# dw08a.net
KiCad netlist of a schematic drawn in EAGLE
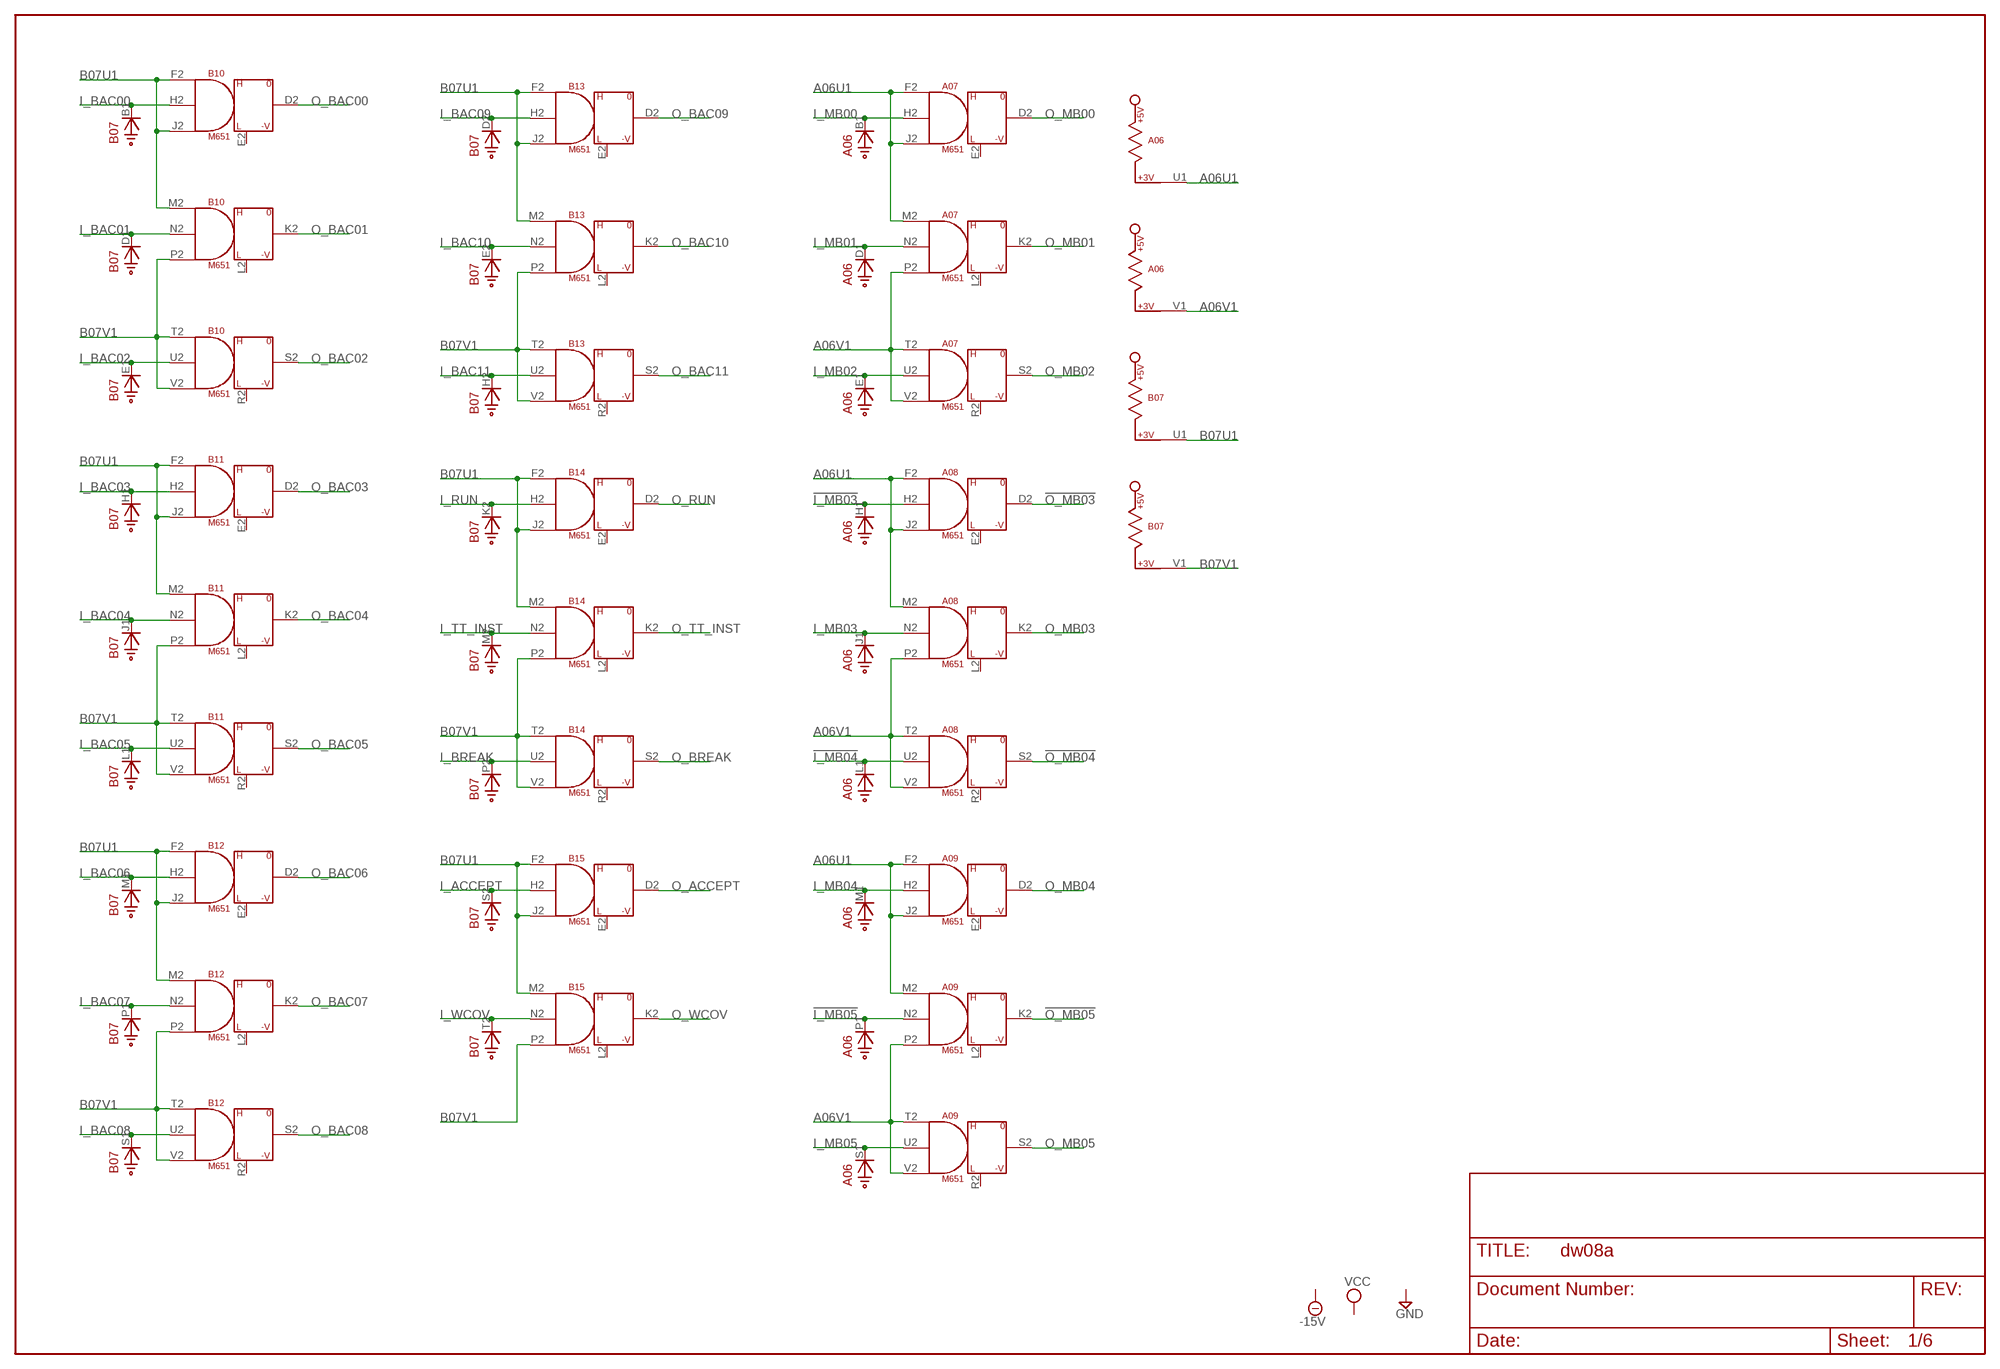
[diagram p0: schematic, sheet 1]
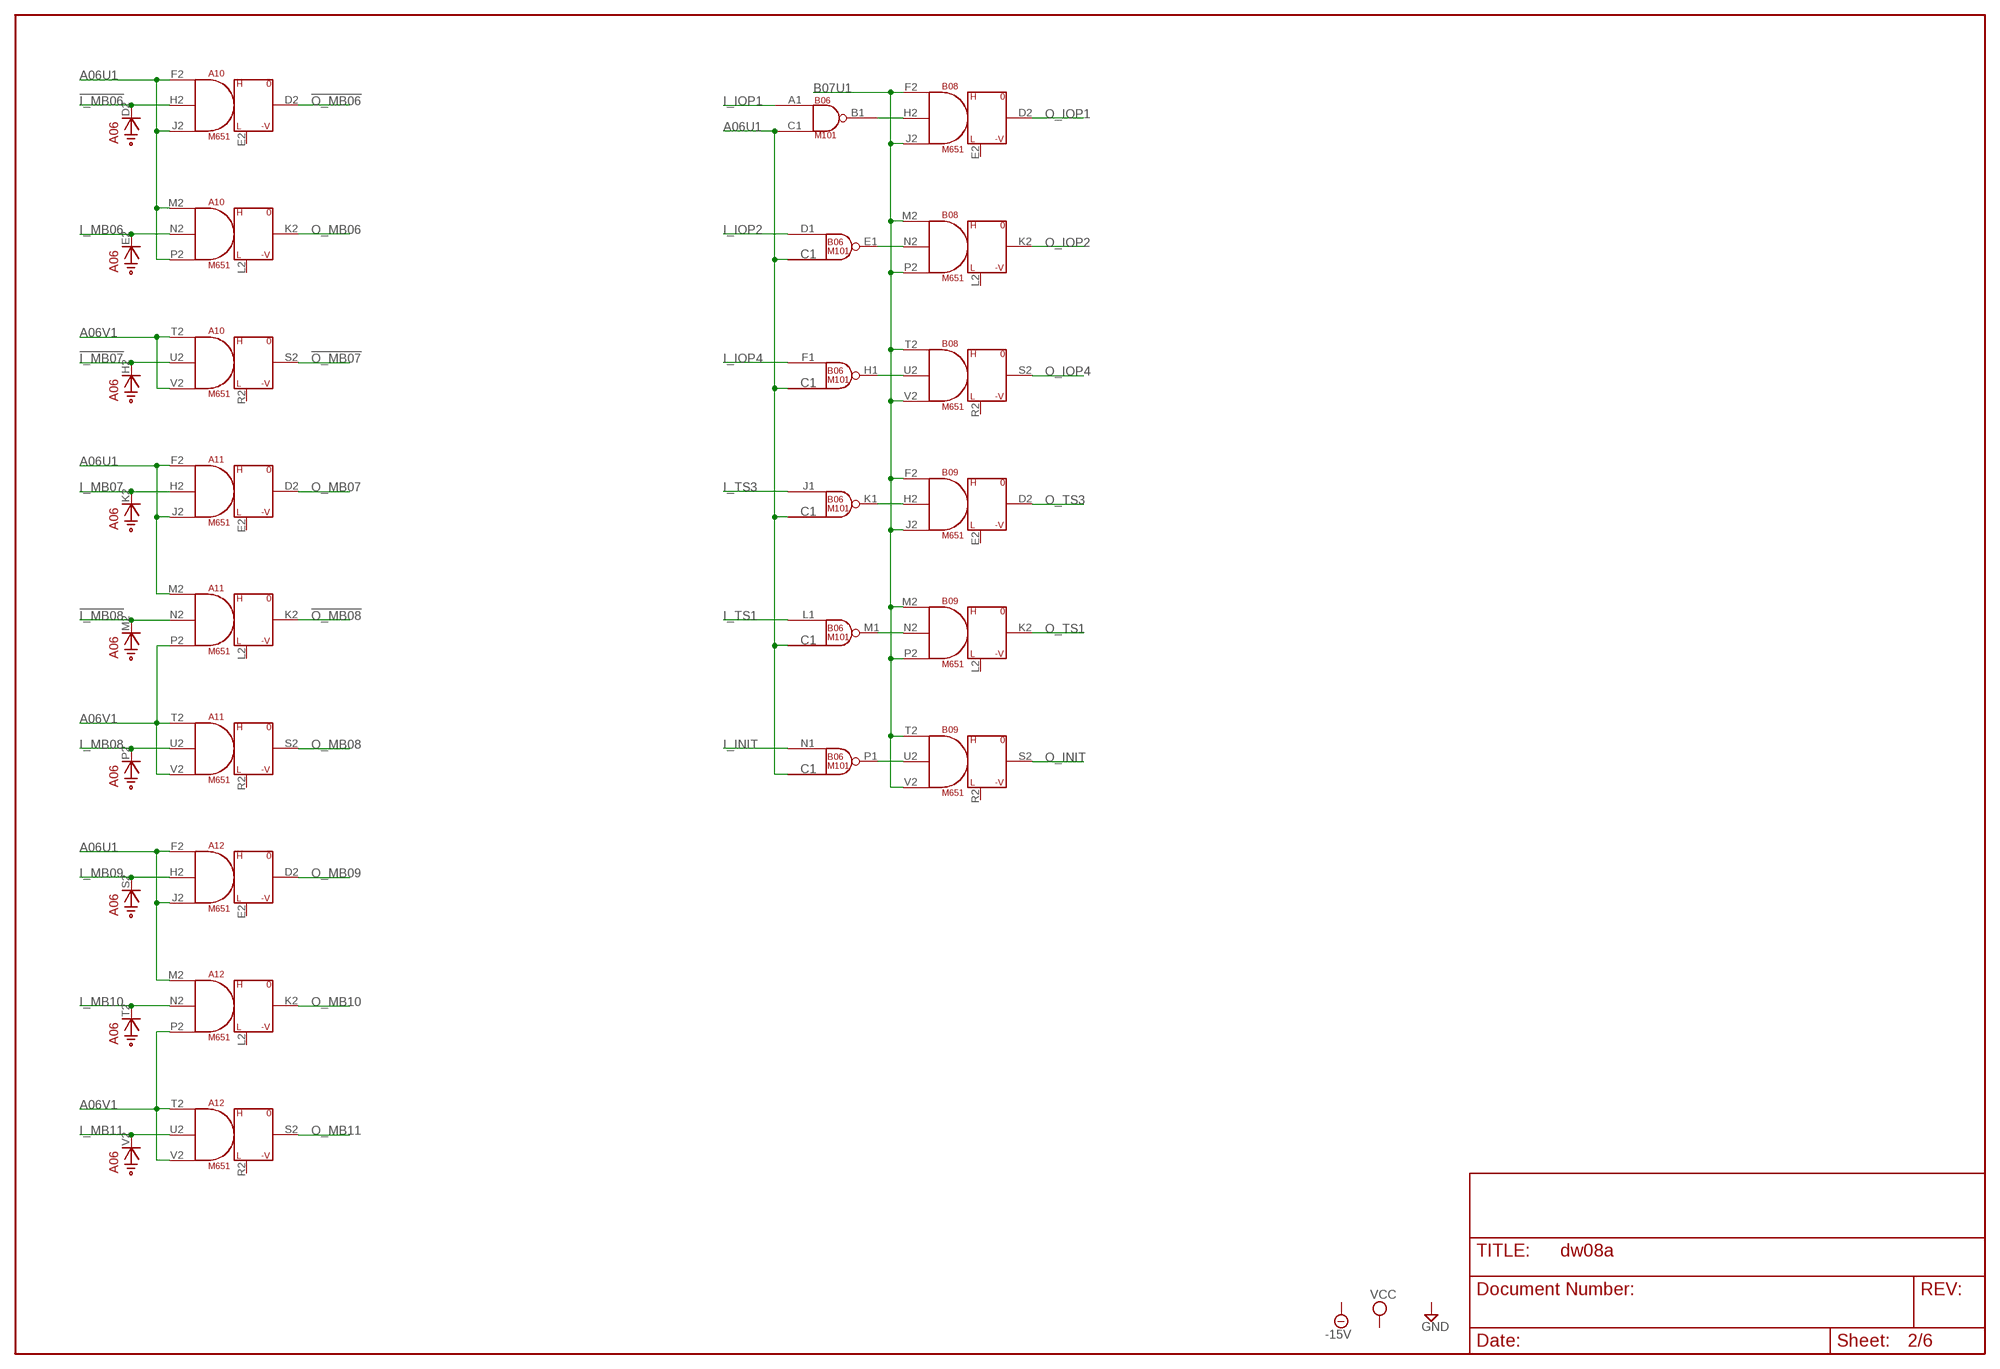
[diagram p1: schematic, sheet 2]
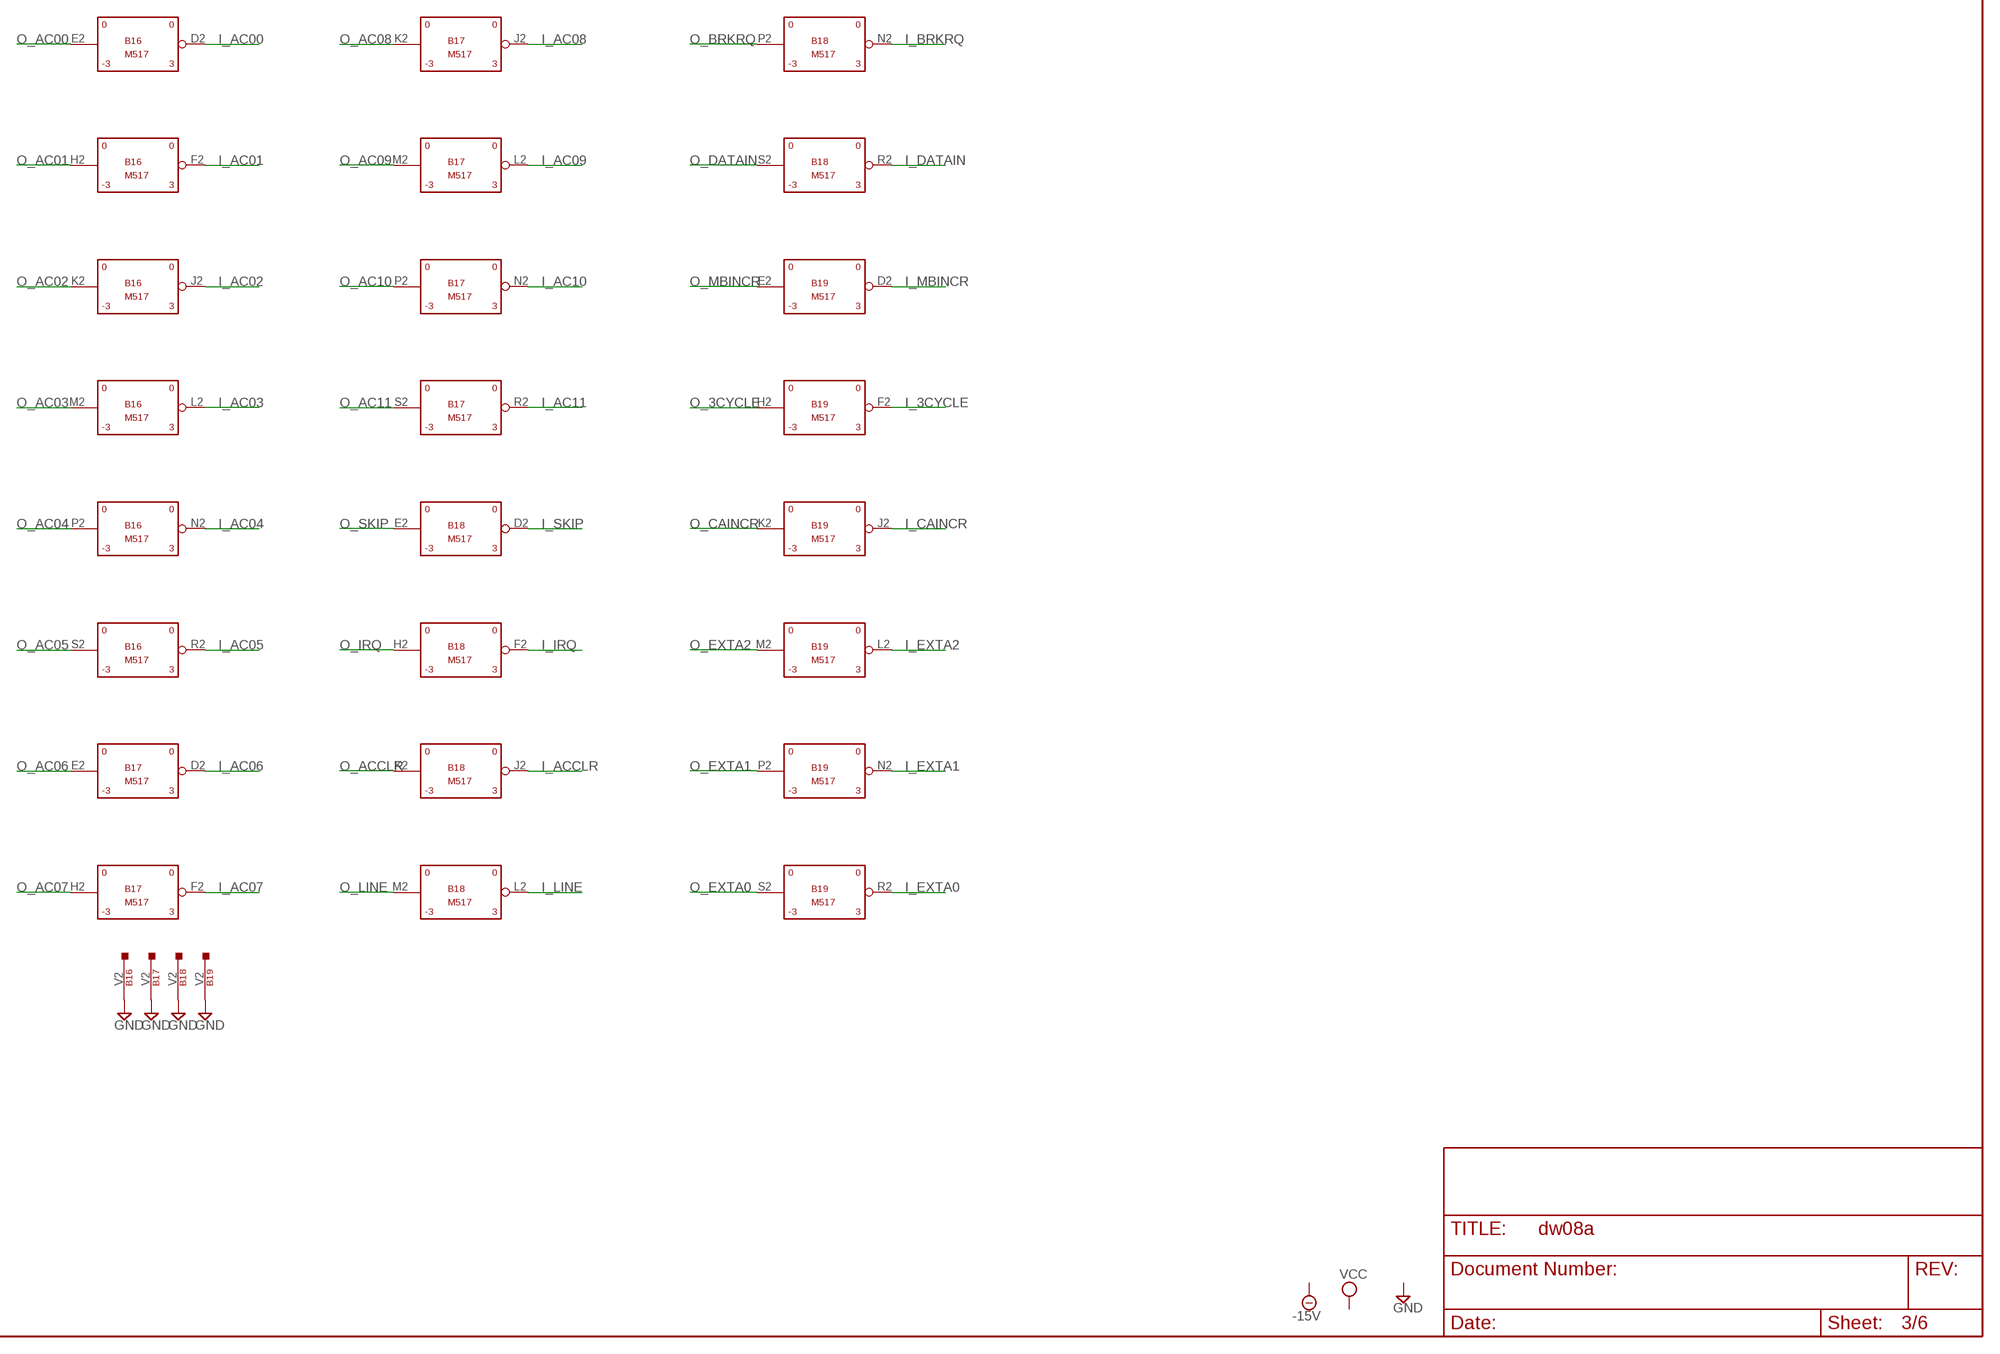
[diagram p2: schematic, sheet 3]
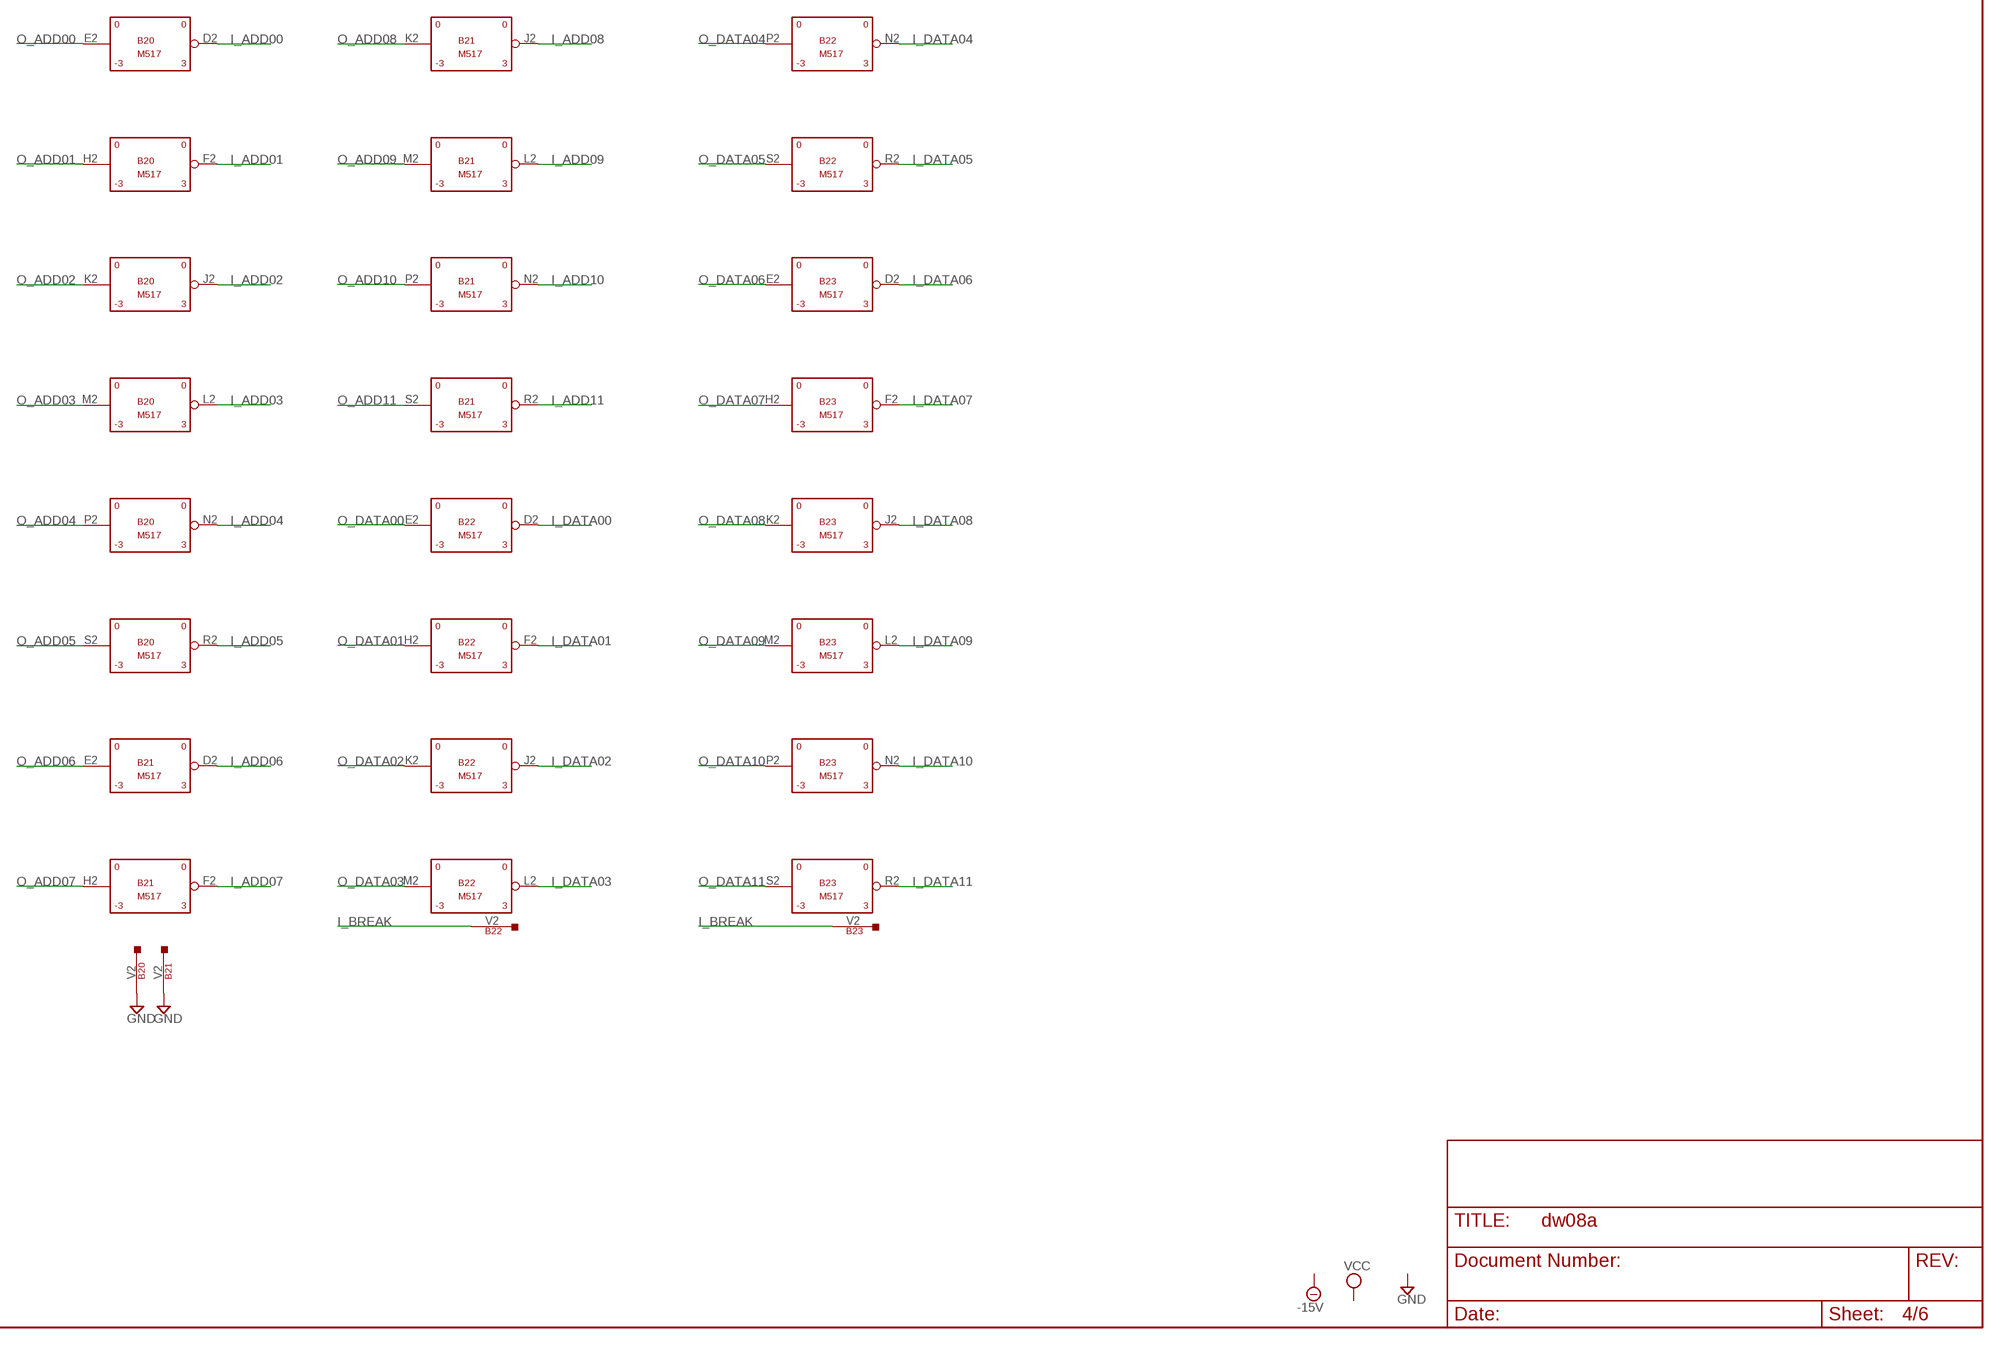
[diagram p3: schematic, sheet 4]
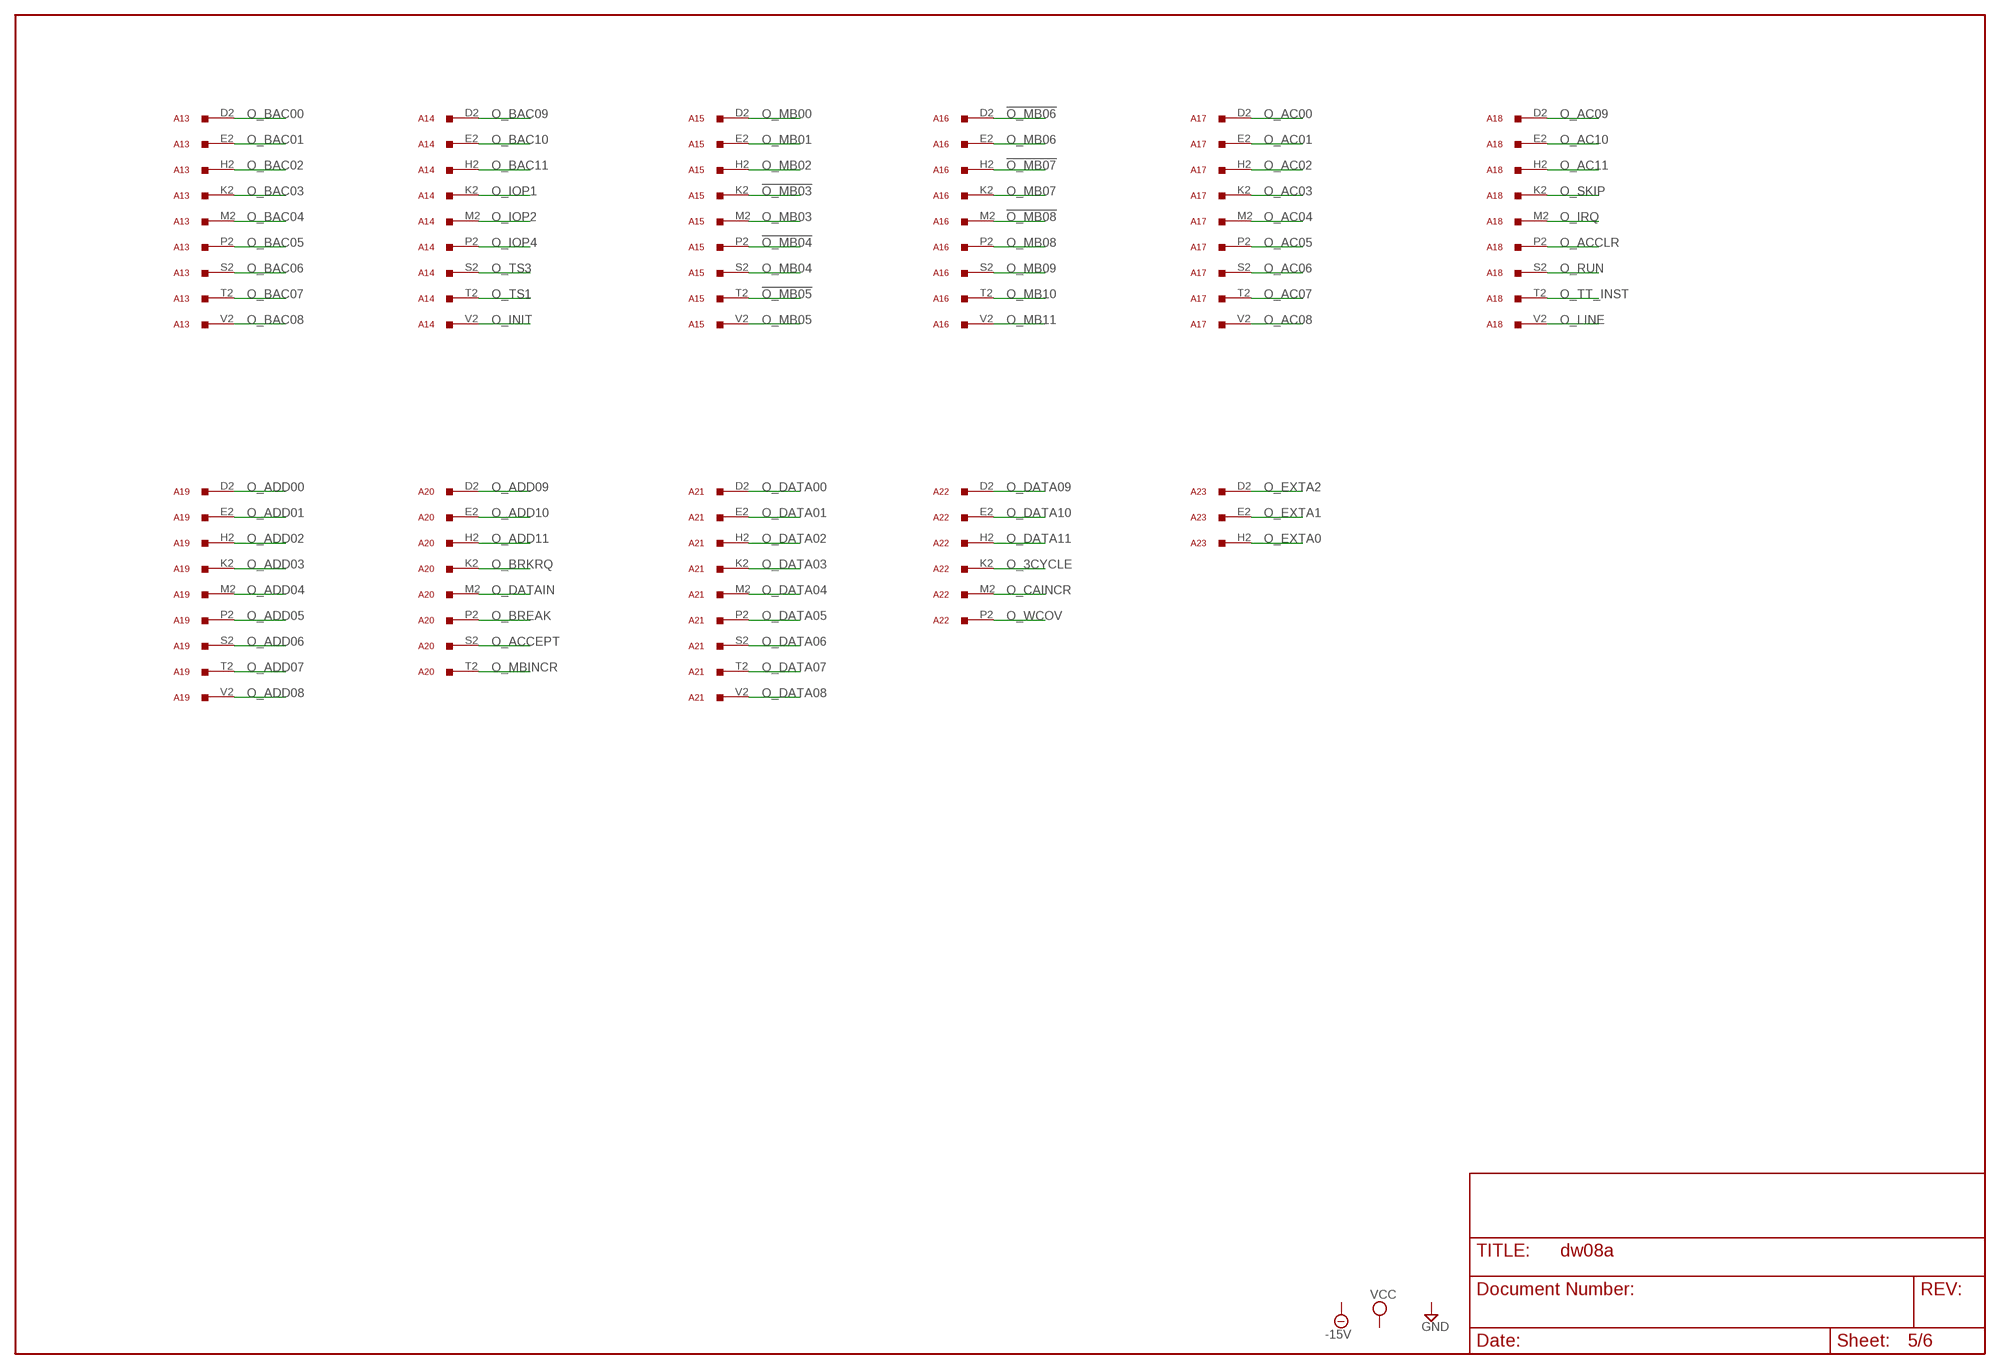
[diagram p4: schematic, sheet 5]
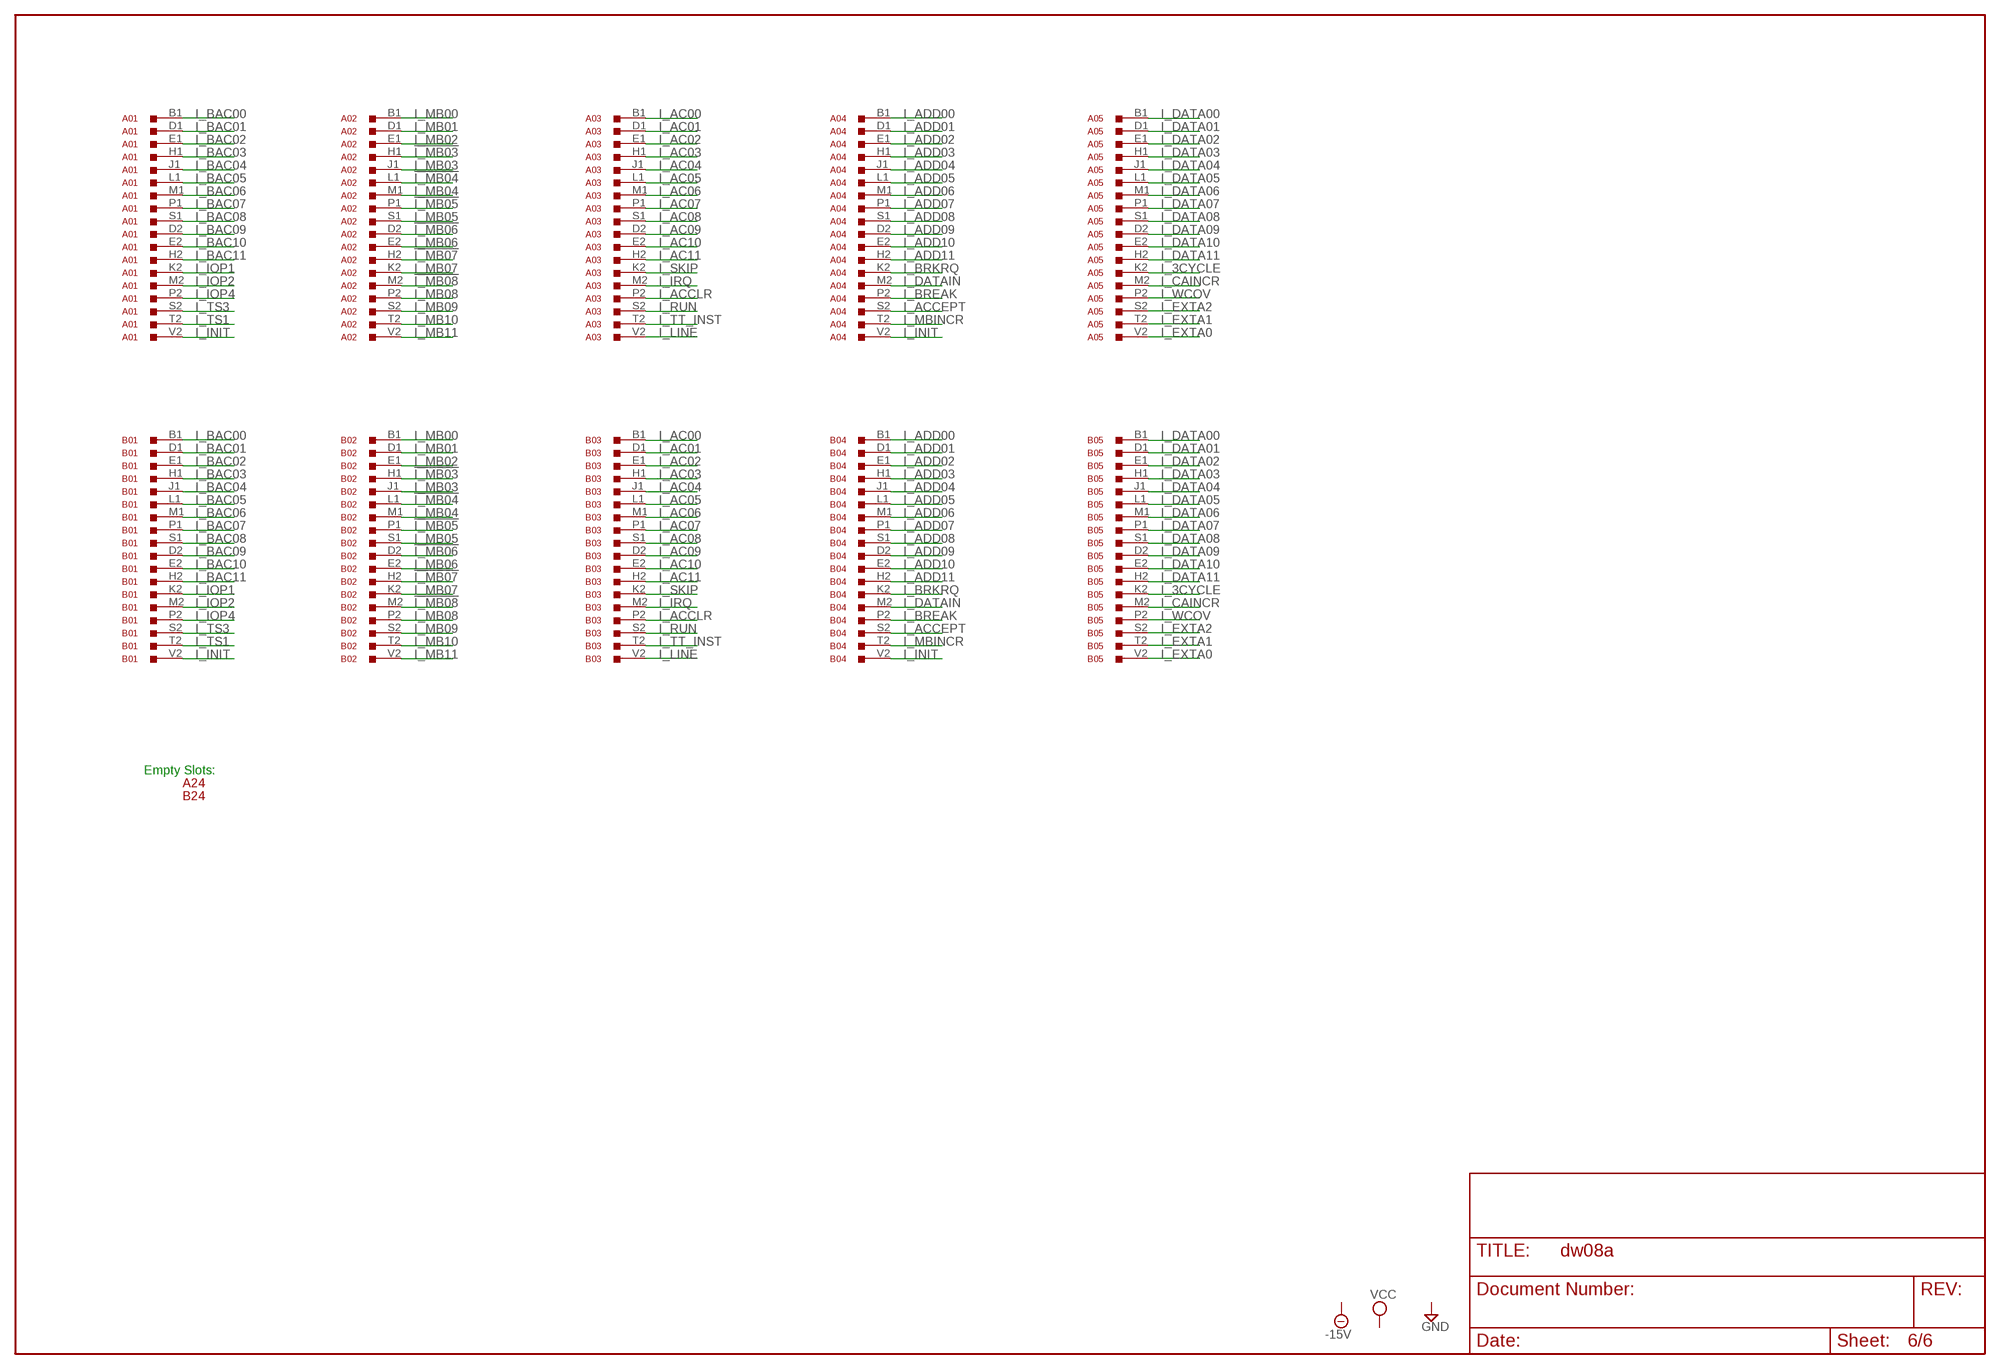
[diagram p5: schematic, sheet 6]

(export (version "E")
  (design (tool "Eeschema 10.0.6"))
  (components
    (comp (ref "A06")
      (value "M907")
      (footprint "eagle-import:H807")
      (libsource (lib "eagle-import") (part "M907"))
    )
    (comp (ref "A07")
      (value "M651")
      (footprint "eagle-import:H807")
      (libsource (lib "eagle-import") (part "M651"))
    )
    (comp (ref "A08")
      (value "M651")
      (footprint "eagle-import:H807")
      (libsource (lib "eagle-import") (part "M651"))
    )
    (comp (ref "A09")
      (value "M651")
      (footprint "eagle-import:H807")
      (libsource (lib "eagle-import") (part "M651"))
    )
    (comp (ref "B07")
      (value "M907")
      (footprint "eagle-import:H807")
      (libsource (lib "eagle-import") (part "M907"))
    )
    (comp (ref "B10")
      (value "M651")
      (footprint "eagle-import:H807")
      (libsource (lib "eagle-import") (part "M651"))
    )
    (comp (ref "B11")
      (value "M651")
      (footprint "eagle-import:H807")
      (libsource (lib "eagle-import") (part "M651"))
    )
    (comp (ref "B12")
      (value "M651")
      (footprint "eagle-import:H807")
      (libsource (lib "eagle-import") (part "M651"))
    )
    (comp (ref "B13")
      (value "M651")
      (footprint "eagle-import:H807")
      (libsource (lib "eagle-import") (part "M651"))
    )
    (comp (ref "B14")
      (value "M651")
      (footprint "eagle-import:H807")
      (libsource (lib "eagle-import") (part "M651"))
    )
    (comp (ref "B15")
      (value "M651")
      (footprint "eagle-import:H807")
      (libsource (lib "eagle-import") (part "M651"))
    )
    (comp (ref "B16")
      (value "M517")
      (footprint "eagle-import:H807")
      (libsource (lib "eagle-import") (part "M517"))
    )
    (comp (ref "B17")
      (value "M517")
      (footprint "eagle-import:H807")
      (libsource (lib "eagle-import") (part "M517"))
    )
    (comp (ref "B18")
      (value "M517")
      (footprint "eagle-import:H807")
      (libsource (lib "eagle-import") (part "M517"))
    )
    (comp (ref "B19")
      (value "M517")
      (footprint "eagle-import:H807")
      (libsource (lib "eagle-import") (part "M517"))
    )
    (comp (ref "A01")
      (value "M903")
      (footprint "eagle-import:H807")
      (libsource (lib "eagle-import") (part "M903"))
    )
    (comp (ref "A02")
      (value "M903")
      (footprint "eagle-import:H807")
      (libsource (lib "eagle-import") (part "M903"))
    )
    (comp (ref "A03")
      (value "M903")
      (footprint "eagle-import:H807")
      (libsource (lib "eagle-import") (part "M903"))
    )
    (comp (ref "A04")
      (value "M903")
      (footprint "eagle-import:H807")
      (libsource (lib "eagle-import") (part "M903"))
    )
    (comp (ref "A05")
      (value "M903")
      (footprint "eagle-import:H807")
      (libsource (lib "eagle-import") (part "M903"))
    )
    (comp (ref "A24")
      (value "H807")
      (footprint "eagle-import:H807")
      (libsource (lib "eagle-import") (part "H807"))
    )
    (comp (ref "B01")
      (value "M903")
      (footprint "eagle-import:H807")
      (libsource (lib "eagle-import") (part "M903"))
    )
    (comp (ref "B02")
      (value "M903")
      (footprint "eagle-import:H807")
      (libsource (lib "eagle-import") (part "M903"))
    )
    (comp (ref "B03")
      (value "M903")
      (footprint "eagle-import:H807")
      (libsource (lib "eagle-import") (part "M903"))
    )
    (comp (ref "B04")
      (value "M903")
      (footprint "eagle-import:H807")
      (libsource (lib "eagle-import") (part "M903"))
    )
    (comp (ref "B05")
      (value "M903")
      (footprint "eagle-import:H807")
      (libsource (lib "eagle-import") (part "M903"))
    )
    (comp (ref "B24")
      (value "H807")
      (footprint "eagle-import:H807")
      (libsource (lib "eagle-import") (part "H807"))
    )
    (comp (ref "A10")
      (value "M651")
      (footprint "eagle-import:H807")
      (libsource (lib "eagle-import") (part "M651"))
    )
    (comp (ref "A11")
      (value "M651")
      (footprint "eagle-import:H807")
      (libsource (lib "eagle-import") (part "M651"))
    )
    (comp (ref "A12")
      (value "M651")
      (footprint "eagle-import:H807")
      (libsource (lib "eagle-import") (part "M651"))
    )
    (comp (ref "B06")
      (value "M101")
      (footprint "eagle-import:H807")
      (libsource (lib "eagle-import") (part "M101"))
    )
    (comp (ref "B08")
      (value "M651")
      (footprint "eagle-import:H807")
      (libsource (lib "eagle-import") (part "M651"))
    )
    (comp (ref "B09")
      (value "M651")
      (footprint "eagle-import:H807")
      (libsource (lib "eagle-import") (part "M651"))
    )
    (comp (ref "B20")
      (value "M517")
      (footprint "eagle-import:H807")
      (libsource (lib "eagle-import") (part "M517"))
    )
    (comp (ref "B21")
      (value "M517")
      (footprint "eagle-import:H807")
      (libsource (lib "eagle-import") (part "M517"))
    )
    (comp (ref "B22")
      (value "M517")
      (footprint "eagle-import:H807")
      (libsource (lib "eagle-import") (part "M517"))
    )
    (comp (ref "B23")
      (value "M517")
      (footprint "eagle-import:H807")
      (libsource (lib "eagle-import") (part "M517"))
    )
    (comp (ref "A13")
      (value "W011")
      (footprint "eagle-import:H807")
      (libsource (lib "eagle-import") (part "W011"))
    )
    (comp (ref "A14")
      (value "W011")
      (footprint "eagle-import:H807")
      (libsource (lib "eagle-import") (part "W011"))
    )
    (comp (ref "A15")
      (value "W011")
      (footprint "eagle-import:H807")
      (libsource (lib "eagle-import") (part "W011"))
    )
    (comp (ref "A16")
      (value "W011")
      (footprint "eagle-import:H807")
      (libsource (lib "eagle-import") (part "W011"))
    )
    (comp (ref "A17")
      (value "W011")
      (footprint "eagle-import:H807")
      (libsource (lib "eagle-import") (part "W011"))
    )
    (comp (ref "A18")
      (value "W011")
      (footprint "eagle-import:H807")
      (libsource (lib "eagle-import") (part "W011"))
    )
    (comp (ref "A19")
      (value "W011")
      (footprint "eagle-import:H807")
      (libsource (lib "eagle-import") (part "W011"))
    )
    (comp (ref "A20")
      (value "W011")
      (footprint "eagle-import:H807")
      (libsource (lib "eagle-import") (part "W011"))
    )
    (comp (ref "A21")
      (value "W011")
      (footprint "eagle-import:H807")
      (libsource (lib "eagle-import") (part "W011"))
    )
    (comp (ref "A22")
      (value "W011")
      (footprint "eagle-import:H807")
      (libsource (lib "eagle-import") (part "W011"))
    )
    (comp (ref "A23")
      (value "W011")
      (footprint "eagle-import:H807")
      (libsource (lib "eagle-import") (part "W011"))
    )
  )
  (nets
    (net (code "2") (name "A06U1") (class "Default")
      (node (ref "A06") (pin "U1") (pinfunction "P$1_U1") (pintype "passive"))
      (node (ref "A07") (pin "F2") (pinfunction "IN1_F2") (pintype "input"))
      (node (ref "A07") (pin "J2") (pinfunction "IN3_J2") (pintype "input"))
      (node (ref "A07") (pin "M2") (pinfunction "IN1_M2") (pintype "input"))
      (node (ref "A08") (pin "F2") (pinfunction "IN1_F2") (pintype "input"))
      (node (ref "A08") (pin "J2") (pinfunction "IN3_J2") (pintype "input"))
      (node (ref "A08") (pin "M2") (pinfunction "IN1_M2") (pintype "input"))
      (node (ref "A09") (pin "F2") (pinfunction "IN1_F2") (pintype "input"))
      (node (ref "A09") (pin "J2") (pinfunction "IN3_J2") (pintype "input"))
      (node (ref "A09") (pin "M2") (pinfunction "IN1_M2") (pintype "input"))
      (node (ref "A10") (pin "F2") (pinfunction "IN1_F2") (pintype "input"))
      (node (ref "A10") (pin "J2") (pinfunction "IN3_J2") (pintype "input"))
      (node (ref "A10") (pin "M2") (pinfunction "IN1_M2") (pintype "input"))
      (node (ref "A10") (pin "P2") (pinfunction "IN3_P2") (pintype "input"))
      (node (ref "A11") (pin "F2") (pinfunction "IN1_F2") (pintype "input"))
      (node (ref "A11") (pin "J2") (pinfunction "IN3_J2") (pintype "input"))
      (node (ref "A11") (pin "M2") (pinfunction "IN1_M2") (pintype "input"))
      (node (ref "A12") (pin "F2") (pinfunction "IN1_F2") (pintype "input"))
      (node (ref "A12") (pin "J2") (pinfunction "IN3_J2") (pintype "input"))
      (node (ref "A12") (pin "M2") (pinfunction "IN1_M2") (pintype "input"))
      (node (ref "B06") (pin "C1") (pinfunction "IN2_C1") (pintype "input"))
    )
    (net (code "3") (name "A06V1") (class "Default")
      (node (ref "A06") (pin "V1") (pinfunction "P$1_V1") (pintype "passive"))
      (node (ref "A07") (pin "P2") (pinfunction "IN3_P2") (pintype "input"))
      (node (ref "A07") (pin "T2") (pinfunction "IN1_T2") (pintype "input"))
      (node (ref "A07") (pin "V2") (pinfunction "IN3_V2") (pintype "input"))
      (node (ref "A08") (pin "P2") (pinfunction "IN3_P2") (pintype "input"))
      (node (ref "A08") (pin "T2") (pinfunction "IN1_T2") (pintype "input"))
      (node (ref "A08") (pin "V2") (pinfunction "IN3_V2") (pintype "input"))
      (node (ref "A09") (pin "P2") (pinfunction "IN3_P2") (pintype "input"))
      (node (ref "A09") (pin "T2") (pinfunction "IN1_T2") (pintype "input"))
      (node (ref "A09") (pin "V2") (pinfunction "IN3_V2") (pintype "input"))
      (node (ref "A10") (pin "T2") (pinfunction "IN1_T2") (pintype "input"))
      (node (ref "A10") (pin "V2") (pinfunction "IN3_V2") (pintype "input"))
      (node (ref "A11") (pin "P2") (pinfunction "IN3_P2") (pintype "input"))
      (node (ref "A11") (pin "T2") (pinfunction "IN1_T2") (pintype "input"))
      (node (ref "A11") (pin "V2") (pinfunction "IN3_V2") (pintype "input"))
      (node (ref "A12") (pin "P2") (pinfunction "IN3_P2") (pintype "input"))
      (node (ref "A12") (pin "T2") (pinfunction "IN1_T2") (pintype "input"))
      (node (ref "A12") (pin "V2") (pinfunction "IN3_V2") (pintype "input"))
    )
    (net (code "4") (name "B07U1") (class "Default")
      (node (ref "B07") (pin "U1") (pinfunction "P$1_U1") (pintype "passive"))
      (node (ref "B08") (pin "F2") (pinfunction "IN1_F2") (pintype "input"))
      (node (ref "B08") (pin "J2") (pinfunction "IN3_J2") (pintype "input"))
      (node (ref "B08") (pin "M2") (pinfunction "IN1_M2") (pintype "input"))
      (node (ref "B08") (pin "P2") (pinfunction "IN3_P2") (pintype "input"))
      (node (ref "B08") (pin "T2") (pinfunction "IN1_T2") (pintype "input"))
      (node (ref "B08") (pin "V2") (pinfunction "IN3_V2") (pintype "input"))
      (node (ref "B09") (pin "F2") (pinfunction "IN1_F2") (pintype "input"))
      (node (ref "B09") (pin "J2") (pinfunction "IN3_J2") (pintype "input"))
      (node (ref "B09") (pin "M2") (pinfunction "IN1_M2") (pintype "input"))
      (node (ref "B09") (pin "P2") (pinfunction "IN3_P2") (pintype "input"))
      (node (ref "B09") (pin "T2") (pinfunction "IN1_T2") (pintype "input"))
      (node (ref "B09") (pin "V2") (pinfunction "IN3_V2") (pintype "input"))
      (node (ref "B10") (pin "F2") (pinfunction "IN1_F2") (pintype "input"))
      (node (ref "B10") (pin "J2") (pinfunction "IN3_J2") (pintype "input"))
      (node (ref "B10") (pin "M2") (pinfunction "IN1_M2") (pintype "input"))
      (node (ref "B11") (pin "F2") (pinfunction "IN1_F2") (pintype "input"))
      (node (ref "B11") (pin "J2") (pinfunction "IN3_J2") (pintype "input"))
      (node (ref "B11") (pin "M2") (pinfunction "IN1_M2") (pintype "input"))
      (node (ref "B12") (pin "F2") (pinfunction "IN1_F2") (pintype "input"))
      (node (ref "B12") (pin "J2") (pinfunction "IN3_J2") (pintype "input"))
      (node (ref "B12") (pin "M2") (pinfunction "IN1_M2") (pintype "input"))
      (node (ref "B13") (pin "F2") (pinfunction "IN1_F2") (pintype "input"))
      (node (ref "B13") (pin "J2") (pinfunction "IN3_J2") (pintype "input"))
      (node (ref "B13") (pin "M2") (pinfunction "IN1_M2") (pintype "input"))
      (node (ref "B14") (pin "F2") (pinfunction "IN1_F2") (pintype "input"))
      (node (ref "B14") (pin "J2") (pinfunction "IN3_J2") (pintype "input"))
      (node (ref "B14") (pin "M2") (pinfunction "IN1_M2") (pintype "input"))
      (node (ref "B15") (pin "F2") (pinfunction "IN1_F2") (pintype "input"))
      (node (ref "B15") (pin "J2") (pinfunction "IN3_J2") (pintype "input"))
      (node (ref "B15") (pin "M2") (pinfunction "IN1_M2") (pintype "input"))
    )
    (net (code "5") (name "B07V1") (class "Default")
      (node (ref "B07") (pin "V1") (pinfunction "P$1_V1") (pintype "passive"))
      (node (ref "B10") (pin "P2") (pinfunction "IN3_P2") (pintype "input"))
      (node (ref "B10") (pin "T2") (pinfunction "IN1_T2") (pintype "input"))
      (node (ref "B10") (pin "V2") (pinfunction "IN3_V2") (pintype "input"))
      (node (ref "B11") (pin "P2") (pinfunction "IN3_P2") (pintype "input"))
      (node (ref "B11") (pin "T2") (pinfunction "IN1_T2") (pintype "input"))
      (node (ref "B11") (pin "V2") (pinfunction "IN3_V2") (pintype "input"))
      (node (ref "B12") (pin "P2") (pinfunction "IN3_P2") (pintype "input"))
      (node (ref "B12") (pin "T2") (pinfunction "IN1_T2") (pintype "input"))
      (node (ref "B12") (pin "V2") (pinfunction "IN3_V2") (pintype "input"))
      (node (ref "B13") (pin "P2") (pinfunction "IN3_P2") (pintype "input"))
      (node (ref "B13") (pin "T2") (pinfunction "IN1_T2") (pintype "input"))
      (node (ref "B13") (pin "V2") (pinfunction "IN3_V2") (pintype "input"))
      (node (ref "B14") (pin "P2") (pinfunction "IN3_P2") (pintype "input"))
      (node (ref "B14") (pin "T2") (pinfunction "IN1_T2") (pintype "input"))
      (node (ref "B14") (pin "V2") (pinfunction "IN3_V2") (pintype "input"))
      (node (ref "B15") (pin "P2") (pinfunction "IN3_P2") (pintype "input"))
    )
    (net (code "6") (name "GND") (class "Default")
      (node (ref "B16") (pin "V2") (pinfunction "P$1_V2") (pintype "input"))
      (node (ref "B17") (pin "V2") (pinfunction "P$1_V2") (pintype "input"))
      (node (ref "B18") (pin "V2") (pinfunction "P$1_V2") (pintype "input"))
      (node (ref "B19") (pin "V2") (pinfunction "P$1_V2") (pintype "input"))
      (node (ref "B20") (pin "V2") (pinfunction "P$1_V2") (pintype "input"))
      (node (ref "B21") (pin "V2") (pinfunction "P$1_V2") (pintype "input"))
    )
    (net (code "7") (name "I_3CYCLE") (class "Default")
      (node (ref "A05") (pin "K2") (pinfunction "P$2_K2") (pintype "bidirectional"))
      (node (ref "B05") (pin "K2") (pinfunction "P$2_K2") (pintype "bidirectional"))
      (node (ref "B19") (pin "F2") (pinfunction "OUT_F2") (pintype "output"))
    )
    (net (code "8") (name "I_AC00") (class "Default")
      (node (ref "A03") (pin "B1") (pinfunction "P$2_B1") (pintype "bidirectional"))
      (node (ref "B03") (pin "B1") (pinfunction "P$2_B1") (pintype "bidirectional"))
      (node (ref "B16") (pin "D2") (pinfunction "OUT_D2") (pintype "output"))
    )
    (net (code "9") (name "I_AC01") (class "Default")
      (node (ref "A03") (pin "D1") (pinfunction "P$2_D1") (pintype "bidirectional"))
      (node (ref "B03") (pin "D1") (pinfunction "P$2_D1") (pintype "bidirectional"))
      (node (ref "B16") (pin "F2") (pinfunction "OUT_F2") (pintype "output"))
    )
    (net (code "10") (name "I_AC02") (class "Default")
      (node (ref "A03") (pin "E1") (pinfunction "P$2_E1") (pintype "bidirectional"))
      (node (ref "B03") (pin "E1") (pinfunction "P$2_E1") (pintype "bidirectional"))
      (node (ref "B16") (pin "J2") (pinfunction "OUT_J2") (pintype "output"))
    )
    (net (code "11") (name "I_AC03") (class "Default")
      (node (ref "A03") (pin "H1") (pinfunction "P$2_H1") (pintype "bidirectional"))
      (node (ref "B03") (pin "H1") (pinfunction "P$2_H1") (pintype "bidirectional"))
      (node (ref "B16") (pin "L2") (pinfunction "OUT_L2") (pintype "output"))
    )
    (net (code "12") (name "I_AC04") (class "Default")
      (node (ref "A03") (pin "J1") (pinfunction "P$2_J1") (pintype "bidirectional"))
      (node (ref "B03") (pin "J1") (pinfunction "P$2_J1") (pintype "bidirectional"))
      (node (ref "B16") (pin "N2") (pinfunction "OUT_N2") (pintype "output"))
    )
    (net (code "13") (name "I_AC05") (class "Default")
      (node (ref "A03") (pin "L1") (pinfunction "P$2_L1") (pintype "bidirectional"))
      (node (ref "B03") (pin "L1") (pinfunction "P$2_L1") (pintype "bidirectional"))
      (node (ref "B16") (pin "R2") (pinfunction "OUT_R2") (pintype "output"))
    )
    (net (code "14") (name "I_AC06") (class "Default")
      (node (ref "A03") (pin "M1") (pinfunction "P$2_M1") (pintype "bidirectional"))
      (node (ref "B03") (pin "M1") (pinfunction "P$2_M1") (pintype "bidirectional"))
      (node (ref "B17") (pin "D2") (pinfunction "OUT_D2") (pintype "output"))
    )
    (net (code "15") (name "I_AC07") (class "Default")
      (node (ref "A03") (pin "P1") (pinfunction "P$2_P1") (pintype "bidirectional"))
      (node (ref "B03") (pin "P1") (pinfunction "P$2_P1") (pintype "bidirectional"))
      (node (ref "B17") (pin "F2") (pinfunction "OUT_F2") (pintype "output"))
    )
    (net (code "16") (name "I_AC08") (class "Default")
      (node (ref "A03") (pin "S1") (pinfunction "P$2_S1") (pintype "bidirectional"))
      (node (ref "B03") (pin "S1") (pinfunction "P$2_S1") (pintype "bidirectional"))
      (node (ref "B17") (pin "J2") (pinfunction "OUT_J2") (pintype "output"))
    )
    (net (code "17") (name "I_AC09") (class "Default")
      (node (ref "A03") (pin "D2") (pinfunction "P$2_D2") (pintype "bidirectional"))
      (node (ref "B03") (pin "D2") (pinfunction "P$2_D2") (pintype "bidirectional"))
      (node (ref "B17") (pin "L2") (pinfunction "OUT_L2") (pintype "output"))
    )
    (net (code "18") (name "I_AC10") (class "Default")
      (node (ref "A03") (pin "E2") (pinfunction "P$2_E2") (pintype "bidirectional"))
      (node (ref "B03") (pin "E2") (pinfunction "P$2_E2") (pintype "bidirectional"))
      (node (ref "B17") (pin "N2") (pinfunction "OUT_N2") (pintype "output"))
    )
    (net (code "19") (name "I_AC11") (class "Default")
      (node (ref "A03") (pin "H2") (pinfunction "P$2_H2") (pintype "bidirectional"))
      (node (ref "B03") (pin "H2") (pinfunction "P$2_H2") (pintype "bidirectional"))
      (node (ref "B17") (pin "R2") (pinfunction "OUT_R2") (pintype "output"))
    )
    (net (code "20") (name "I_ACCEPT") (class "Default")
      (node (ref "A04") (pin "S2") (pinfunction "P$2_S2") (pintype "bidirectional"))
      (node (ref "B04") (pin "S2") (pinfunction "P$2_S2") (pintype "bidirectional"))
      (node (ref "B07") (pin "S2") (pinfunction "CATHODE_S2") (pintype "passive"))
      (node (ref "B15") (pin "H2") (pinfunction "IN2_H2") (pintype "input"))
    )
    (net (code "21") (name "I_ACCLR") (class "Default")
      (node (ref "A03") (pin "P2") (pinfunction "P$2_P2") (pintype "bidirectional"))
      (node (ref "B03") (pin "P2") (pinfunction "P$2_P2") (pintype "bidirectional"))
      (node (ref "B18") (pin "J2") (pinfunction "OUT_J2") (pintype "output"))
    )
    (net (code "22") (name "I_ADD00") (class "Default")
      (node (ref "A04") (pin "B1") (pinfunction "P$2_B1") (pintype "bidirectional"))
      (node (ref "B04") (pin "B1") (pinfunction "P$2_B1") (pintype "bidirectional"))
      (node (ref "B20") (pin "D2") (pinfunction "OUT_D2") (pintype "output"))
    )
    (net (code "23") (name "I_ADD01") (class "Default")
      (node (ref "A04") (pin "D1") (pinfunction "P$2_D1") (pintype "bidirectional"))
      (node (ref "B04") (pin "D1") (pinfunction "P$2_D1") (pintype "bidirectional"))
      (node (ref "B20") (pin "F2") (pinfunction "OUT_F2") (pintype "output"))
    )
    (net (code "24") (name "I_ADD02") (class "Default")
      (node (ref "A04") (pin "E1") (pinfunction "P$2_E1") (pintype "bidirectional"))
      (node (ref "B04") (pin "E1") (pinfunction "P$2_E1") (pintype "bidirectional"))
      (node (ref "B20") (pin "J2") (pinfunction "OUT_J2") (pintype "output"))
    )
    (net (code "25") (name "I_ADD03") (class "Default")
      (node (ref "A04") (pin "H1") (pinfunction "P$2_H1") (pintype "bidirectional"))
      (node (ref "B04") (pin "H1") (pinfunction "P$2_H1") (pintype "bidirectional"))
      (node (ref "B20") (pin "L2") (pinfunction "OUT_L2") (pintype "output"))
    )
    (net (code "26") (name "I_ADD04") (class "Default")
      (node (ref "A04") (pin "J1") (pinfunction "P$2_J1") (pintype "bidirectional"))
      (node (ref "B04") (pin "J1") (pinfunction "P$2_J1") (pintype "bidirectional"))
      (node (ref "B20") (pin "N2") (pinfunction "OUT_N2") (pintype "output"))
    )
    (net (code "27") (name "I_ADD05") (class "Default")
      (node (ref "A04") (pin "L1") (pinfunction "P$2_L1") (pintype "bidirectional"))
      (node (ref "B04") (pin "L1") (pinfunction "P$2_L1") (pintype "bidirectional"))
      (node (ref "B20") (pin "R2") (pinfunction "OUT_R2") (pintype "output"))
    )
    (net (code "28") (name "I_ADD06") (class "Default")
      (node (ref "A04") (pin "M1") (pinfunction "P$2_M1") (pintype "bidirectional"))
      (node (ref "B04") (pin "M1") (pinfunction "P$2_M1") (pintype "bidirectional"))
      (node (ref "B21") (pin "D2") (pinfunction "OUT_D2") (pintype "output"))
    )
    (net (code "29") (name "I_ADD07") (class "Default")
      (node (ref "A04") (pin "P1") (pinfunction "P$2_P1") (pintype "bidirectional"))
      (node (ref "B04") (pin "P1") (pinfunction "P$2_P1") (pintype "bidirectional"))
      (node (ref "B21") (pin "F2") (pinfunction "OUT_F2") (pintype "output"))
    )
    (net (code "30") (name "I_ADD08") (class "Default")
      (node (ref "A04") (pin "S1") (pinfunction "P$2_S1") (pintype "bidirectional"))
      (node (ref "B04") (pin "S1") (pinfunction "P$2_S1") (pintype "bidirectional"))
      (node (ref "B21") (pin "J2") (pinfunction "OUT_J2") (pintype "output"))
    )
    (net (code "31") (name "I_ADD09") (class "Default")
      (node (ref "A04") (pin "D2") (pinfunction "P$2_D2") (pintype "bidirectional"))
      (node (ref "B04") (pin "D2") (pinfunction "P$2_D2") (pintype "bidirectional"))
      (node (ref "B21") (pin "L2") (pinfunction "OUT_L2") (pintype "output"))
    )
    (net (code "32") (name "I_ADD10") (class "Default")
      (node (ref "A04") (pin "E2") (pinfunction "P$2_E2") (pintype "bidirectional"))
      (node (ref "B04") (pin "E2") (pinfunction "P$2_E2") (pintype "bidirectional"))
      (node (ref "B21") (pin "N2") (pinfunction "OUT_N2") (pintype "output"))
    )
    (net (code "33") (name "I_ADD11") (class "Default")
      (node (ref "A04") (pin "H2") (pinfunction "P$2_H2") (pintype "bidirectional"))
      (node (ref "B04") (pin "H2") (pinfunction "P$2_H2") (pintype "bidirectional"))
      (node (ref "B21") (pin "R2") (pinfunction "OUT_R2") (pintype "output"))
    )
    (net (code "34") (name "I_BAC00") (class "Default")
      (node (ref "A01") (pin "B1") (pinfunction "P$2_B1") (pintype "bidirectional"))
      (node (ref "B01") (pin "B1") (pinfunction "P$2_B1") (pintype "bidirectional"))
      (node (ref "B07") (pin "B1") (pinfunction "CATHODE_B1") (pintype "passive"))
      (node (ref "B10") (pin "H2") (pinfunction "IN2_H2") (pintype "input"))
    )
    (net (code "35") (name "I_BAC01") (class "Default")
      (node (ref "A01") (pin "D1") (pinfunction "P$2_D1") (pintype "bidirectional"))
      (node (ref "B01") (pin "D1") (pinfunction "P$2_D1") (pintype "bidirectional"))
      (node (ref "B07") (pin "D1") (pinfunction "CATHODE_D1") (pintype "passive"))
      (node (ref "B10") (pin "N2") (pinfunction "IN2_N2") (pintype "input"))
    )
    (net (code "36") (name "I_BAC02") (class "Default")
      (node (ref "A01") (pin "E1") (pinfunction "P$2_E1") (pintype "bidirectional"))
      (node (ref "B01") (pin "E1") (pinfunction "P$2_E1") (pintype "bidirectional"))
      (node (ref "B07") (pin "E1") (pinfunction "CATHODE_E1") (pintype "passive"))
      (node (ref "B10") (pin "U2") (pinfunction "IN2_U2") (pintype "input"))
    )
    (net (code "37") (name "I_BAC03") (class "Default")
      (node (ref "A01") (pin "H1") (pinfunction "P$2_H1") (pintype "bidirectional"))
      (node (ref "B01") (pin "H1") (pinfunction "P$2_H1") (pintype "bidirectional"))
      (node (ref "B07") (pin "H1") (pinfunction "CATHODE_H1") (pintype "passive"))
      (node (ref "B11") (pin "H2") (pinfunction "IN2_H2") (pintype "input"))
    )
    (net (code "38") (name "I_BAC04") (class "Default")
      (node (ref "A01") (pin "J1") (pinfunction "P$2_J1") (pintype "bidirectional"))
      (node (ref "B01") (pin "J1") (pinfunction "P$2_J1") (pintype "bidirectional"))
      (node (ref "B07") (pin "J1") (pinfunction "CATHODE_J1") (pintype "passive"))
      (node (ref "B11") (pin "N2") (pinfunction "IN2_N2") (pintype "input"))
    )
    (net (code "39") (name "I_BAC05") (class "Default")
      (node (ref "A01") (pin "L1") (pinfunction "P$2_L1") (pintype "bidirectional"))
      (node (ref "B01") (pin "L1") (pinfunction "P$2_L1") (pintype "bidirectional"))
      (node (ref "B07") (pin "L1") (pinfunction "CATHODE_L1") (pintype "passive"))
      (node (ref "B11") (pin "U2") (pinfunction "IN2_U2") (pintype "input"))
    )
    (net (code "40") (name "I_BAC06") (class "Default")
      (node (ref "A01") (pin "M1") (pinfunction "P$2_M1") (pintype "bidirectional"))
      (node (ref "B01") (pin "M1") (pinfunction "P$2_M1") (pintype "bidirectional"))
      (node (ref "B07") (pin "M1") (pinfunction "CATHODE_M1") (pintype "passive"))
      (node (ref "B12") (pin "H2") (pinfunction "IN2_H2") (pintype "input"))
    )
    (net (code "41") (name "I_BAC07") (class "Default")
      (node (ref "A01") (pin "P1") (pinfunction "P$2_P1") (pintype "bidirectional"))
      (node (ref "B01") (pin "P1") (pinfunction "P$2_P1") (pintype "bidirectional"))
      (node (ref "B07") (pin "P1") (pinfunction "CATHODE_P1") (pintype "passive"))
      (node (ref "B12") (pin "N2") (pinfunction "IN2_N2") (pintype "input"))
    )
    (net (code "42") (name "I_BAC08") (class "Default")
      (node (ref "A01") (pin "S1") (pinfunction "P$2_S1") (pintype "bidirectional"))
      (node (ref "B01") (pin "S1") (pinfunction "P$2_S1") (pintype "bidirectional"))
      (node (ref "B07") (pin "S1") (pinfunction "CATHODE_S1") (pintype "passive"))
      (node (ref "B12") (pin "U2") (pinfunction "IN2_U2") (pintype "input"))
    )
    (net (code "43") (name "I_BAC09") (class "Default")
      (node (ref "A01") (pin "D2") (pinfunction "P$2_D2") (pintype "bidirectional"))
      (node (ref "B01") (pin "D2") (pinfunction "P$2_D2") (pintype "bidirectional"))
      (node (ref "B07") (pin "D2") (pinfunction "CATHODE_D2") (pintype "passive"))
      (node (ref "B13") (pin "H2") (pinfunction "IN2_H2") (pintype "input"))
    )
    (net (code "44") (name "I_BAC10") (class "Default")
      (node (ref "A01") (pin "E2") (pinfunction "P$2_E2") (pintype "bidirectional"))
      (node (ref "B01") (pin "E2") (pinfunction "P$2_E2") (pintype "bidirectional"))
      (node (ref "B07") (pin "E2") (pinfunction "CATHODE_E2") (pintype "passive"))
      (node (ref "B13") (pin "N2") (pinfunction "IN2_N2") (pintype "input"))
    )
    (net (code "45") (name "I_BAC11") (class "Default")
      (node (ref "A01") (pin "H2") (pinfunction "P$2_H2") (pintype "bidirectional"))
      (node (ref "B01") (pin "H2") (pinfunction "P$2_H2") (pintype "bidirectional"))
      (node (ref "B07") (pin "H2") (pinfunction "CATHODE_H2") (pintype "passive"))
      (node (ref "B13") (pin "U2") (pinfunction "IN2_U2") (pintype "input"))
    )
    (net (code "46") (name "I_BREAK") (class "Default")
      (node (ref "A04") (pin "P2") (pinfunction "P$2_P2") (pintype "bidirectional"))
      (node (ref "B04") (pin "P2") (pinfunction "P$2_P2") (pintype "bidirectional"))
      (node (ref "B07") (pin "P2") (pinfunction "CATHODE_P2") (pintype "passive"))
      (node (ref "B14") (pin "U2") (pinfunction "IN2_U2") (pintype "input"))
      (node (ref "B22") (pin "V2") (pinfunction "P$1_V2") (pintype "input"))
      (node (ref "B23") (pin "V2") (pinfunction "P$1_V2") (pintype "input"))
    )
    (net (code "47") (name "I_BRKRQ") (class "Default")
      (node (ref "A04") (pin "K2") (pinfunction "P$2_K2") (pintype "bidirectional"))
      (node (ref "B04") (pin "K2") (pinfunction "P$2_K2") (pintype "bidirectional"))
      (node (ref "B18") (pin "N2") (pinfunction "OUT_N2") (pintype "output"))
    )
    (net (code "48") (name "I_CAINCR") (class "Default")
      (node (ref "A05") (pin "M2") (pinfunction "P$2_M2") (pintype "bidirectional"))
      (node (ref "B05") (pin "M2") (pinfunction "P$2_M2") (pintype "bidirectional"))
      (node (ref "B19") (pin "J2") (pinfunction "OUT_J2") (pintype "output"))
    )
    (net (code "49") (name "I_DATA00") (class "Default")
      (node (ref "A05") (pin "B1") (pinfunction "P$2_B1") (pintype "bidirectional"))
      (node (ref "B05") (pin "B1") (pinfunction "P$2_B1") (pintype "bidirectional"))
      (node (ref "B22") (pin "D2") (pinfunction "OUT_D2") (pintype "output"))
    )
    (net (code "50") (name "I_DATA01") (class "Default")
      (node (ref "A05") (pin "D1") (pinfunction "P$2_D1") (pintype "bidirectional"))
      (node (ref "B05") (pin "D1") (pinfunction "P$2_D1") (pintype "bidirectional"))
      (node (ref "B22") (pin "F2") (pinfunction "OUT_F2") (pintype "output"))
    )
    (net (code "51") (name "I_DATA02") (class "Default")
      (node (ref "A05") (pin "E1") (pinfunction "P$2_E1") (pintype "bidirectional"))
      (node (ref "B05") (pin "E1") (pinfunction "P$2_E1") (pintype "bidirectional"))
      (node (ref "B22") (pin "J2") (pinfunction "OUT_J2") (pintype "output"))
    )
    (net (code "52") (name "I_DATA03") (class "Default")
      (node (ref "A05") (pin "H1") (pinfunction "P$2_H1") (pintype "bidirectional"))
      (node (ref "B05") (pin "H1") (pinfunction "P$2_H1") (pintype "bidirectional"))
      (node (ref "B22") (pin "L2") (pinfunction "OUT_L2") (pintype "output"))
    )
    (net (code "53") (name "I_DATA04") (class "Default")
      (node (ref "A05") (pin "J1") (pinfunction "P$2_J1") (pintype "bidirectional"))
      (node (ref "B05") (pin "J1") (pinfunction "P$2_J1") (pintype "bidirectional"))
      (node (ref "B22") (pin "N2") (pinfunction "OUT_N2") (pintype "output"))
    )
    (net (code "54") (name "I_DATA05") (class "Default")
      (node (ref "A05") (pin "L1") (pinfunction "P$2_L1") (pintype "bidirectional"))
      (node (ref "B05") (pin "L1") (pinfunction "P$2_L1") (pintype "bidirectional"))
      (node (ref "B22") (pin "R2") (pinfunction "OUT_R2") (pintype "output"))
    )
    (net (code "55") (name "I_DATA06") (class "Default")
      (node (ref "A05") (pin "M1") (pinfunction "P$2_M1") (pintype "bidirectional"))
      (node (ref "B05") (pin "M1") (pinfunction "P$2_M1") (pintype "bidirectional"))
      (node (ref "B23") (pin "D2") (pinfunction "OUT_D2") (pintype "output"))
    )
    (net (code "56") (name "I_DATA07") (class "Default")
      (node (ref "A05") (pin "P1") (pinfunction "P$2_P1") (pintype "bidirectional"))
      (node (ref "B05") (pin "P1") (pinfunction "P$2_P1") (pintype "bidirectional"))
      (node (ref "B23") (pin "F2") (pinfunction "OUT_F2") (pintype "output"))
    )
    (net (code "57") (name "I_DATA08") (class "Default")
      (node (ref "A05") (pin "S1") (pinfunction "P$2_S1") (pintype "bidirectional"))
      (node (ref "B05") (pin "S1") (pinfunction "P$2_S1") (pintype "bidirectional"))
      (node (ref "B23") (pin "J2") (pinfunction "OUT_J2") (pintype "output"))
    )
    (net (code "58") (name "I_DATA09") (class "Default")
      (node (ref "A05") (pin "D2") (pinfunction "P$2_D2") (pintype "bidirectional"))
      (node (ref "B05") (pin "D2") (pinfunction "P$2_D2") (pintype "bidirectional"))
      (node (ref "B23") (pin "L2") (pinfunction "OUT_L2") (pintype "output"))
    )
    (net (code "59") (name "I_DATA10") (class "Default")
      (node (ref "A05") (pin "E2") (pinfunction "P$2_E2") (pintype "bidirectional"))
      (node (ref "B05") (pin "E2") (pinfunction "P$2_E2") (pintype "bidirectional"))
      (node (ref "B23") (pin "N2") (pinfunction "OUT_N2") (pintype "output"))
    )
    (net (code "60") (name "I_DATA11") (class "Default")
      (node (ref "A05") (pin "H2") (pinfunction "P$2_H2") (pintype "bidirectional"))
      (node (ref "B05") (pin "H2") (pinfunction "P$2_H2") (pintype "bidirectional"))
      (node (ref "B23") (pin "R2") (pinfunction "OUT_R2") (pintype "output"))
    )
    (net (code "61") (name "I_DATAIN") (class "Default")
      (node (ref "A04") (pin "M2") (pinfunction "P$2_M2") (pintype "bidirectional"))
      (node (ref "B04") (pin "M2") (pinfunction "P$2_M2") (pintype "bidirectional"))
      (node (ref "B18") (pin "R2") (pinfunction "OUT_R2") (pintype "output"))
    )
    (net (code "62") (name "I_EXTA0") (class "Default")
      (node (ref "A05") (pin "V2") (pinfunction "P$2_V2") (pintype "bidirectional"))
      (node (ref "B05") (pin "V2") (pinfunction "P$2_V2") (pintype "bidirectional"))
      (node (ref "B19") (pin "R2") (pinfunction "OUT_R2") (pintype "output"))
    )
    (net (code "63") (name "I_EXTA1") (class "Default")
      (node (ref "A05") (pin "T2") (pinfunction "P$2_T2") (pintype "bidirectional"))
      (node (ref "B05") (pin "T2") (pinfunction "P$2_T2") (pintype "bidirectional"))
      (node (ref "B19") (pin "N2") (pinfunction "OUT_N2") (pintype "output"))
    )
    (net (code "64") (name "I_EXTA2") (class "Default")
      (node (ref "A05") (pin "S2") (pinfunction "P$2_S2") (pintype "bidirectional"))
      (node (ref "B05") (pin "S2") (pinfunction "P$2_S2") (pintype "bidirectional"))
      (node (ref "B19") (pin "L2") (pinfunction "OUT_L2") (pintype "output"))
    )
    (net (code "65") (name "I_INIT") (class "Default")
      (node (ref "A01") (pin "V2") (pinfunction "P$2_V2") (pintype "bidirectional"))
      (node (ref "A04") (pin "V2") (pinfunction "P$2_V2") (pintype "bidirectional"))
      (node (ref "B01") (pin "V2") (pinfunction "P$2_V2") (pintype "bidirectional"))
      (node (ref "B04") (pin "V2") (pinfunction "P$2_V2") (pintype "bidirectional"))
      (node (ref "B06") (pin "N1") (pinfunction "IN_N1") (pintype "input"))
    )
    (net (code "66") (name "I_IOP1") (class "Default")
      (node (ref "A01") (pin "K2") (pinfunction "P$2_K2") (pintype "bidirectional"))
      (node (ref "B01") (pin "K2") (pinfunction "P$2_K2") (pintype "bidirectional"))
      (node (ref "B06") (pin "A1") (pinfunction "IN1_A1") (pintype "input"))
    )
    (net (code "67") (name "I_IOP2") (class "Default")
      (node (ref "A01") (pin "M2") (pinfunction "P$2_M2") (pintype "bidirectional"))
      (node (ref "B01") (pin "M2") (pinfunction "P$2_M2") (pintype "bidirectional"))
      (node (ref "B06") (pin "D1") (pinfunction "IN_D1") (pintype "input"))
    )
    (net (code "68") (name "I_IOP4") (class "Default")
      (node (ref "A01") (pin "P2") (pinfunction "P$2_P2") (pintype "bidirectional"))
      (node (ref "B01") (pin "P2") (pinfunction "P$2_P2") (pintype "bidirectional"))
      (node (ref "B06") (pin "F1") (pinfunction "IN_F1") (pintype "input"))
    )
    (net (code "69") (name "I_IRQ") (class "Default")
      (node (ref "A03") (pin "M2") (pinfunction "P$2_M2") (pintype "bidirectional"))
      (node (ref "B03") (pin "M2") (pinfunction "P$2_M2") (pintype "bidirectional"))
      (node (ref "B18") (pin "F2") (pinfunction "OUT_F2") (pintype "output"))
    )
    (net (code "70") (name "I_LINE") (class "Default")
      (node (ref "A03") (pin "V2") (pinfunction "P$2_V2") (pintype "bidirectional"))
      (node (ref "B03") (pin "V2") (pinfunction "P$2_V2") (pintype "bidirectional"))
      (node (ref "B18") (pin "L2") (pinfunction "OUT_L2") (pintype "output"))
    )
    (net (code "71") (name "I_MB00") (class "Default")
      (node (ref "A02") (pin "B1") (pinfunction "P$2_B1") (pintype "bidirectional"))
      (node (ref "A06") (pin "B1") (pinfunction "CATHODE_B1") (pintype "passive"))
      (node (ref "A07") (pin "H2") (pinfunction "IN2_H2") (pintype "input"))
      (node (ref "B02") (pin "B1") (pinfunction "P$2_B1") (pintype "bidirectional"))
    )
    (net (code "72") (name "I_MB01") (class "Default")
      (node (ref "A02") (pin "D1") (pinfunction "P$2_D1") (pintype "bidirectional"))
      (node (ref "A06") (pin "D1") (pinfunction "CATHODE_D1") (pintype "passive"))
      (node (ref "A07") (pin "N2") (pinfunction "IN2_N2") (pintype "input"))
      (node (ref "B02") (pin "D1") (pinfunction "P$2_D1") (pintype "bidirectional"))
    )
    (net (code "73") (name "I_MB02") (class "Default")
      (node (ref "A02") (pin "E1") (pinfunction "P$2_E1") (pintype "bidirectional"))
      (node (ref "A06") (pin "E1") (pinfunction "CATHODE_E1") (pintype "passive"))
      (node (ref "A07") (pin "U2") (pinfunction "IN2_U2") (pintype "input"))
      (node (ref "B02") (pin "E1") (pinfunction "P$2_E1") (pintype "bidirectional"))
    )
    (net (code "74") (name "I_MB03") (class "Default")
      (node (ref "A02") (pin "J1") (pinfunction "P$2_J1") (pintype "bidirectional"))
      (node (ref "A06") (pin "J1") (pinfunction "CATHODE_J1") (pintype "passive"))
      (node (ref "A08") (pin "N2") (pinfunction "IN2_N2") (pintype "input"))
      (node (ref "B02") (pin "J1") (pinfunction "P$2_J1") (pintype "bidirectional"))
    )
    (net (code "75") (name "I_MB04") (class "Default")
      (node (ref "A02") (pin "M1") (pinfunction "P$2_M1") (pintype "bidirectional"))
      (node (ref "A06") (pin "M1") (pinfunction "CATHODE_M1") (pintype "passive"))
      (node (ref "A09") (pin "H2") (pinfunction "IN2_H2") (pintype "input"))
      (node (ref "B02") (pin "M1") (pinfunction "P$2_M1") (pintype "bidirectional"))
    )
    (net (code "76") (name "I_MB05") (class "Default")
      (node (ref "A02") (pin "S1") (pinfunction "P$2_S1") (pintype "bidirectional"))
      (node (ref "A06") (pin "S1") (pinfunction "CATHODE_S1") (pintype "passive"))
      (node (ref "A09") (pin "U2") (pinfunction "IN2_U2") (pintype "input"))
      (node (ref "B02") (pin "S1") (pinfunction "P$2_S1") (pintype "bidirectional"))
    )
    (net (code "77") (name "I_MB06") (class "Default")
      (node (ref "A02") (pin "E2") (pinfunction "P$2_E2") (pintype "bidirectional"))
      (node (ref "A06") (pin "E2") (pinfunction "CATHODE_E2") (pintype "passive"))
      (node (ref "A10") (pin "N2") (pinfunction "IN2_N2") (pintype "input"))
      (node (ref "B02") (pin "E2") (pinfunction "P$2_E2") (pintype "bidirectional"))
    )
    (net (code "78") (name "I_MB07") (class "Default")
      (node (ref "A02") (pin "K2") (pinfunction "P$2_K2") (pintype "bidirectional"))
      (node (ref "A06") (pin "K2") (pinfunction "CATHODE_K2") (pintype "passive"))
      (node (ref "A11") (pin "H2") (pinfunction "IN2_H2") (pintype "input"))
      (node (ref "B02") (pin "K2") (pinfunction "P$2_K2") (pintype "bidirectional"))
    )
    (net (code "79") (name "I_MB08") (class "Default")
      (node (ref "A02") (pin "P2") (pinfunction "P$2_P2") (pintype "bidirectional"))
      (node (ref "A06") (pin "P2") (pinfunction "CATHODE_P2") (pintype "passive"))
      (node (ref "A11") (pin "U2") (pinfunction "IN2_U2") (pintype "input"))
      (node (ref "B02") (pin "P2") (pinfunction "P$2_P2") (pintype "bidirectional"))
    )
    (net (code "80") (name "I_MB09") (class "Default")
      (node (ref "A02") (pin "S2") (pinfunction "P$2_S2") (pintype "bidirectional"))
      (node (ref "A06") (pin "S2") (pinfunction "CATHODE_S2") (pintype "passive"))
      (node (ref "A12") (pin "H2") (pinfunction "IN2_H2") (pintype "input"))
      (node (ref "B02") (pin "S2") (pinfunction "P$2_S2") (pintype "bidirectional"))
    )
    (net (code "81") (name "I_MB10") (class "Default")
      (node (ref "A02") (pin "T2") (pinfunction "P$2_T2") (pintype "bidirectional"))
      (node (ref "A06") (pin "T2") (pinfunction "CATHODE_T2") (pintype "passive"))
      (node (ref "A12") (pin "N2") (pinfunction "IN2_N2") (pintype "input"))
      (node (ref "B02") (pin "T2") (pinfunction "P$2_T2") (pintype "bidirectional"))
    )
    (net (code "82") (name "I_MB11") (class "Default")
      (node (ref "A02") (pin "V2") (pinfunction "P$2_V2") (pintype "bidirectional"))
      (node (ref "A06") (pin "V2") (pinfunction "CATHODE_V2") (pintype "passive"))
      (node (ref "A12") (pin "U2") (pinfunction "IN2_U2") (pintype "input"))
      (node (ref "B02") (pin "V2") (pinfunction "P$2_V2") (pintype "bidirectional"))
    )
    (net (code "83") (name "I_MBINCR") (class "Default")
      (node (ref "A04") (pin "T2") (pinfunction "P$2_T2") (pintype "bidirectional"))
      (node (ref "B04") (pin "T2") (pinfunction "P$2_T2") (pintype "bidirectional"))
      (node (ref "B19") (pin "D2") (pinfunction "OUT_D2") (pintype "output"))
    )
    (net (code "84") (name "I_RUN") (class "Default")
      (node (ref "A03") (pin "S2") (pinfunction "P$2_S2") (pintype "bidirectional"))
      (node (ref "B03") (pin "S2") (pinfunction "P$2_S2") (pintype "bidirectional"))
      (node (ref "B07") (pin "K2") (pinfunction "CATHODE_K2") (pintype "passive"))
      (node (ref "B14") (pin "H2") (pinfunction "IN2_H2") (pintype "input"))
    )
    (net (code "85") (name "I_SKIP") (class "Default")
      (node (ref "A03") (pin "K2") (pinfunction "P$2_K2") (pintype "bidirectional"))
      (node (ref "B03") (pin "K2") (pinfunction "P$2_K2") (pintype "bidirectional"))
      (node (ref "B18") (pin "D2") (pinfunction "OUT_D2") (pintype "output"))
    )
    (net (code "86") (name "I_TS1") (class "Default")
      (node (ref "A01") (pin "T2") (pinfunction "P$2_T2") (pintype "bidirectional"))
      (node (ref "B01") (pin "T2") (pinfunction "P$2_T2") (pintype "bidirectional"))
      (node (ref "B06") (pin "L1") (pinfunction "IN_L1") (pintype "input"))
    )
    (net (code "87") (name "I_TS3") (class "Default")
      (node (ref "A01") (pin "S2") (pinfunction "P$2_S2") (pintype "bidirectional"))
      (node (ref "B01") (pin "S2") (pinfunction "P$2_S2") (pintype "bidirectional"))
      (node (ref "B06") (pin "J1") (pinfunction "IN_J1") (pintype "input"))
    )
    (net (code "88") (name "I_TT_INST") (class "Default")
      (node (ref "A03") (pin "T2") (pinfunction "P$2_T2") (pintype "bidirectional"))
      (node (ref "B03") (pin "T2") (pinfunction "P$2_T2") (pintype "bidirectional"))
      (node (ref "B07") (pin "M2") (pinfunction "CATHODE_M2") (pintype "passive"))
      (node (ref "B14") (pin "N2") (pinfunction "IN2_N2") (pintype "input"))
    )
    (net (code "89") (name "I_WCOV") (class "Default")
      (node (ref "A05") (pin "P2") (pinfunction "P$2_P2") (pintype "bidirectional"))
      (node (ref "B05") (pin "P2") (pinfunction "P$2_P2") (pintype "bidirectional"))
      (node (ref "B07") (pin "T2") (pinfunction "CATHODE_T2") (pintype "passive"))
      (node (ref "B15") (pin "N2") (pinfunction "IN2_N2") (pintype "input"))
    )
    (net (code "90") (name "Net-(B06A-OUT)") (class "Default")
      (node (ref "B06") (pin "B1") (pinfunction "OUT_B1") (pintype "output"))
      (node (ref "B08") (pin "H2") (pinfunction "IN2_H2") (pintype "input"))
    )
    (net (code "91") (name "Net-(B06B-OUT)") (class "Default")
      (node (ref "B06") (pin "E1") (pinfunction "OUT_E1") (pintype "output"))
      (node (ref "B08") (pin "N2") (pinfunction "IN2_N2") (pintype "input"))
    )
    (net (code "92") (name "Net-(B06F-OUT)") (class "Default")
      (node (ref "B06") (pin "H1") (pinfunction "OUT_H1") (pintype "output"))
      (node (ref "B08") (pin "U2") (pinfunction "IN2_U2") (pintype "input"))
    )
    (net (code "93") (name "Net-(B06H-OUT)") (class "Default")
      (node (ref "B06") (pin "K1") (pinfunction "OUT_K1") (pintype "output"))
      (node (ref "B09") (pin "H2") (pinfunction "IN2_H2") (pintype "input"))
    )
    (net (code "94") (name "Net-(B06J-OUT)") (class "Default")
      (node (ref "B06") (pin "M1") (pinfunction "OUT_M1") (pintype "output"))
      (node (ref "B09") (pin "N2") (pinfunction "IN2_N2") (pintype "input"))
    )
    (net (code "95") (name "Net-(B06L-OUT)") (class "Default")
      (node (ref "B06") (pin "P1") (pinfunction "OUT_P1") (pintype "output"))
      (node (ref "B09") (pin "U2") (pinfunction "IN2_U2") (pintype "input"))
    )
    (net (code "96") (name "O_3CYCLE") (class "Default")
      (node (ref "A22") (pin "K2") (pinfunction "P$2_K2") (pintype "bidirectional"))
      (node (ref "B19") (pin "H2") (pinfunction "IN_H2") (pintype "input"))
    )
    (net (code "97") (name "O_AC00") (class "Default")
      (node (ref "A17") (pin "D2") (pinfunction "P$2_D2") (pintype "bidirectional"))
      (node (ref "B16") (pin "E2") (pinfunction "IN_E2") (pintype "input"))
    )
    (net (code "98") (name "O_AC01") (class "Default")
      (node (ref "A17") (pin "E2") (pinfunction "P$2_E2") (pintype "bidirectional"))
      (node (ref "B16") (pin "H2") (pinfunction "IN_H2") (pintype "input"))
    )
    (net (code "99") (name "O_AC02") (class "Default")
      (node (ref "A17") (pin "H2") (pinfunction "P$2_H2") (pintype "bidirectional"))
      (node (ref "B16") (pin "K2") (pinfunction "IN_K2") (pintype "input"))
    )
    (net (code "100") (name "O_AC03") (class "Default")
      (node (ref "A17") (pin "K2") (pinfunction "P$2_K2") (pintype "bidirectional"))
      (node (ref "B16") (pin "M2") (pinfunction "IN_M2") (pintype "input"))
    )
    (net (code "101") (name "O_AC04") (class "Default")
      (node (ref "A17") (pin "M2") (pinfunction "P$2_M2") (pintype "bidirectional"))
      (node (ref "B16") (pin "P2") (pinfunction "IN_P2") (pintype "input"))
    )
    (net (code "102") (name "O_AC05") (class "Default")
      (node (ref "A17") (pin "P2") (pinfunction "P$2_P2") (pintype "bidirectional"))
      (node (ref "B16") (pin "S2") (pinfunction "IN_S2") (pintype "input"))
    )
    (net (code "103") (name "O_AC06") (class "Default")
      (node (ref "A17") (pin "S2") (pinfunction "P$2_S2") (pintype "bidirectional"))
      (node (ref "B17") (pin "E2") (pinfunction "IN_E2") (pintype "input"))
    )
    (net (code "104") (name "O_AC07") (class "Default")
      (node (ref "A17") (pin "T2") (pinfunction "P$2_T2") (pintype "bidirectional"))
      (node (ref "B17") (pin "H2") (pinfunction "IN_H2") (pintype "input"))
    )
    (net (code "105") (name "O_AC08") (class "Default")
      (node (ref "A17") (pin "V2") (pinfunction "P$2_V2") (pintype "bidirectional"))
      (node (ref "B17") (pin "K2") (pinfunction "IN_K2") (pintype "input"))
    )
    (net (code "106") (name "O_AC09") (class "Default")
      (node (ref "A18") (pin "D2") (pinfunction "P$2_D2") (pintype "bidirectional"))
      (node (ref "B17") (pin "M2") (pinfunction "IN_M2") (pintype "input"))
    )
    (net (code "107") (name "O_AC10") (class "Default")
      (node (ref "A18") (pin "E2") (pinfunction "P$2_E2") (pintype "bidirectional"))
      (node (ref "B17") (pin "P2") (pinfunction "IN_P2") (pintype "input"))
    )
    (net (code "108") (name "O_AC11") (class "Default")
      (node (ref "A18") (pin "H2") (pinfunction "P$2_H2") (pintype "bidirectional"))
      (node (ref "B17") (pin "S2") (pinfunction "IN_S2") (pintype "input"))
    )
    (net (code "109") (name "O_ACCEPT") (class "Default")
      (node (ref "A20") (pin "S2") (pinfunction "P$2_S2") (pintype "bidirectional"))
      (node (ref "B15") (pin "D2") (pinfunction "OUT_D2") (pintype "output"))
    )
    (net (code "110") (name "O_ACCLR") (class "Default")
      (node (ref "A18") (pin "P2") (pinfunction "P$2_P2") (pintype "bidirectional"))
      (node (ref "B18") (pin "K2") (pinfunction "IN_K2") (pintype "input"))
    )
    (net (code "111") (name "O_ADD00") (class "Default")
      (node (ref "A19") (pin "D2") (pinfunction "P$2_D2") (pintype "bidirectional"))
      (node (ref "B20") (pin "E2") (pinfunction "IN_E2") (pintype "input"))
    )
    (net (code "112") (name "O_ADD01") (class "Default")
      (node (ref "A19") (pin "E2") (pinfunction "P$2_E2") (pintype "bidirectional"))
      (node (ref "B20") (pin "H2") (pinfunction "IN_H2") (pintype "input"))
    )
    (net (code "113") (name "O_ADD02") (class "Default")
      (node (ref "A19") (pin "H2") (pinfunction "P$2_H2") (pintype "bidirectional"))
      (node (ref "B20") (pin "K2") (pinfunction "IN_K2") (pintype "input"))
    )
    (net (code "114") (name "O_ADD03") (class "Default")
      (node (ref "A19") (pin "K2") (pinfunction "P$2_K2") (pintype "bidirectional"))
      (node (ref "B20") (pin "M2") (pinfunction "IN_M2") (pintype "input"))
    )
    (net (code "115") (name "O_ADD04") (class "Default")
      (node (ref "A19") (pin "M2") (pinfunction "P$2_M2") (pintype "bidirectional"))
      (node (ref "B20") (pin "P2") (pinfunction "IN_P2") (pintype "input"))
    )
    (net (code "116") (name "O_ADD05") (class "Default")
      (node (ref "A19") (pin "P2") (pinfunction "P$2_P2") (pintype "bidirectional"))
      (node (ref "B20") (pin "S2") (pinfunction "IN_S2") (pintype "input"))
    )
    (net (code "117") (name "O_ADD06") (class "Default")
      (node (ref "A19") (pin "S2") (pinfunction "P$2_S2") (pintype "bidirectional"))
      (node (ref "B21") (pin "E2") (pinfunction "IN_E2") (pintype "input"))
    )
    (net (code "118") (name "O_ADD07") (class "Default")
      (node (ref "A19") (pin "T2") (pinfunction "P$2_T2") (pintype "bidirectional"))
      (node (ref "B21") (pin "H2") (pinfunction "IN_H2") (pintype "input"))
    )
    (net (code "119") (name "O_ADD08") (class "Default")
      (node (ref "A19") (pin "V2") (pinfunction "P$2_V2") (pintype "bidirectional"))
      (node (ref "B21") (pin "K2") (pinfunction "IN_K2") (pintype "input"))
    )
    (net (code "120") (name "O_ADD09") (class "Default")
      (node (ref "A20") (pin "D2") (pinfunction "P$2_D2") (pintype "bidirectional"))
      (node (ref "B21") (pin "M2") (pinfunction "IN_M2") (pintype "input"))
    )
    (net (code "121") (name "O_ADD10") (class "Default")
      (node (ref "A20") (pin "E2") (pinfunction "P$2_E2") (pintype "bidirectional"))
      (node (ref "B21") (pin "P2") (pinfunction "IN_P2") (pintype "input"))
    )
    (net (code "122") (name "O_ADD11") (class "Default")
      (node (ref "A20") (pin "H2") (pinfunction "P$2_H2") (pintype "bidirectional"))
      (node (ref "B21") (pin "S2") (pinfunction "IN_S2") (pintype "input"))
    )
    (net (code "123") (name "O_BAC00") (class "Default")
      (node (ref "A13") (pin "D2") (pinfunction "P$2_D2") (pintype "bidirectional"))
      (node (ref "B10") (pin "D2") (pinfunction "OUT_D2") (pintype "output"))
    )
    (net (code "124") (name "O_BAC01") (class "Default")
      (node (ref "A13") (pin "E2") (pinfunction "P$2_E2") (pintype "bidirectional"))
      (node (ref "B10") (pin "K2") (pinfunction "OUT_K2") (pintype "output"))
    )
    (net (code "125") (name "O_BAC02") (class "Default")
      (node (ref "A13") (pin "H2") (pinfunction "P$2_H2") (pintype "bidirectional"))
      (node (ref "B10") (pin "S2") (pinfunction "OUT_S2") (pintype "output"))
    )
    (net (code "126") (name "O_BAC03") (class "Default")
      (node (ref "A13") (pin "K2") (pinfunction "P$2_K2") (pintype "bidirectional"))
      (node (ref "B11") (pin "D2") (pinfunction "OUT_D2") (pintype "output"))
    )
    (net (code "127") (name "O_BAC04") (class "Default")
      (node (ref "A13") (pin "M2") (pinfunction "P$2_M2") (pintype "bidirectional"))
      (node (ref "B11") (pin "K2") (pinfunction "OUT_K2") (pintype "output"))
    )
    (net (code "128") (name "O_BAC05") (class "Default")
      (node (ref "A13") (pin "P2") (pinfunction "P$2_P2") (pintype "bidirectional"))
      (node (ref "B11") (pin "S2") (pinfunction "OUT_S2") (pintype "output"))
    )
    (net (code "129") (name "O_BAC06") (class "Default")
      (node (ref "A13") (pin "S2") (pinfunction "P$2_S2") (pintype "bidirectional"))
      (node (ref "B12") (pin "D2") (pinfunction "OUT_D2") (pintype "output"))
    )
    (net (code "130") (name "O_BAC07") (class "Default")
      (node (ref "A13") (pin "T2") (pinfunction "P$2_T2") (pintype "bidirectional"))
      (node (ref "B12") (pin "K2") (pinfunction "OUT_K2") (pintype "output"))
    )
    (net (code "131") (name "O_BAC08") (class "Default")
      (node (ref "A13") (pin "V2") (pinfunction "P$2_V2") (pintype "bidirectional"))
      (node (ref "B12") (pin "S2") (pinfunction "OUT_S2") (pintype "output"))
    )
    (net (code "132") (name "O_BAC09") (class "Default")
      (node (ref "A14") (pin "D2") (pinfunction "P$2_D2") (pintype "bidirectional"))
      (node (ref "B13") (pin "D2") (pinfunction "OUT_D2") (pintype "output"))
    )
    (net (code "133") (name "O_BAC10") (class "Default")
      (node (ref "A14") (pin "E2") (pinfunction "P$2_E2") (pintype "bidirectional"))
      (node (ref "B13") (pin "K2") (pinfunction "OUT_K2") (pintype "output"))
    )
    (net (code "134") (name "O_BAC11") (class "Default")
      (node (ref "A14") (pin "H2") (pinfunction "P$2_H2") (pintype "bidirectional"))
      (node (ref "B13") (pin "S2") (pinfunction "OUT_S2") (pintype "output"))
    )
    (net (code "135") (name "O_BREAK") (class "Default")
      (node (ref "A20") (pin "P2") (pinfunction "P$2_P2") (pintype "bidirectional"))
      (node (ref "B14") (pin "S2") (pinfunction "OUT_S2") (pintype "output"))
    )
    (net (code "136") (name "O_BRKRQ") (class "Default")
      (node (ref "A20") (pin "K2") (pinfunction "P$2_K2") (pintype "bidirectional"))
      (node (ref "B18") (pin "P2") (pinfunction "IN_P2") (pintype "input"))
    )
    (net (code "137") (name "O_CAINCR") (class "Default")
      (node (ref "A22") (pin "M2") (pinfunction "P$2_M2") (pintype "bidirectional"))
      (node (ref "B19") (pin "K2") (pinfunction "IN_K2") (pintype "input"))
    )
    (net (code "138") (name "O_DATA00") (class "Default")
      (node (ref "A21") (pin "D2") (pinfunction "P$2_D2") (pintype "bidirectional"))
      (node (ref "B22") (pin "E2") (pinfunction "IN_E2") (pintype "input"))
    )
    (net (code "139") (name "O_DATA01") (class "Default")
      (node (ref "A21") (pin "E2") (pinfunction "P$2_E2") (pintype "bidirectional"))
      (node (ref "B22") (pin "H2") (pinfunction "IN_H2") (pintype "input"))
    )
    (net (code "140") (name "O_DATA02") (class "Default")
      (node (ref "A21") (pin "H2") (pinfunction "P$2_H2") (pintype "bidirectional"))
      (node (ref "B22") (pin "K2") (pinfunction "IN_K2") (pintype "input"))
    )
    (net (code "141") (name "O_DATA03") (class "Default")
      (node (ref "A21") (pin "K2") (pinfunction "P$2_K2") (pintype "bidirectional"))
      (node (ref "B22") (pin "M2") (pinfunction "IN_M2") (pintype "input"))
    )
    (net (code "142") (name "O_DATA04") (class "Default")
      (node (ref "A21") (pin "M2") (pinfunction "P$2_M2") (pintype "bidirectional"))
      (node (ref "B22") (pin "P2") (pinfunction "IN_P2") (pintype "input"))
    )
    (net (code "143") (name "O_DATA05") (class "Default")
      (node (ref "A21") (pin "P2") (pinfunction "P$2_P2") (pintype "bidirectional"))
      (node (ref "B22") (pin "S2") (pinfunction "IN_S2") (pintype "input"))
    )
    (net (code "144") (name "O_DATA06") (class "Default")
      (node (ref "A21") (pin "S2") (pinfunction "P$2_S2") (pintype "bidirectional"))
      (node (ref "B23") (pin "E2") (pinfunction "IN_E2") (pintype "input"))
    )
    (net (code "145") (name "O_DATA07") (class "Default")
      (node (ref "A21") (pin "T2") (pinfunction "P$2_T2") (pintype "bidirectional"))
      (node (ref "B23") (pin "H2") (pinfunction "IN_H2") (pintype "input"))
    )
    (net (code "146") (name "O_DATA08") (class "Default")
      (node (ref "A21") (pin "V2") (pinfunction "P$2_V2") (pintype "bidirectional"))
      (node (ref "B23") (pin "K2") (pinfunction "IN_K2") (pintype "input"))
    )
    (net (code "147") (name "O_DATA09") (class "Default")
      (node (ref "A22") (pin "D2") (pinfunction "P$2_D2") (pintype "bidirectional"))
      (node (ref "B23") (pin "M2") (pinfunction "IN_M2") (pintype "input"))
    )
    (net (code "148") (name "O_DATA10") (class "Default")
      (node (ref "A22") (pin "E2") (pinfunction "P$2_E2") (pintype "bidirectional"))
      (node (ref "B23") (pin "P2") (pinfunction "IN_P2") (pintype "input"))
    )
    (net (code "149") (name "O_DATA11") (class "Default")
      (node (ref "A22") (pin "H2") (pinfunction "P$2_H2") (pintype "bidirectional"))
      (node (ref "B23") (pin "S2") (pinfunction "IN_S2") (pintype "input"))
    )
    (net (code "150") (name "O_DATAIN") (class "Default")
      (node (ref "A20") (pin "M2") (pinfunction "P$2_M2") (pintype "bidirectional"))
      (node (ref "B18") (pin "S2") (pinfunction "IN_S2") (pintype "input"))
    )
    (net (code "151") (name "O_EXTA0") (class "Default")
      (node (ref "A23") (pin "H2") (pinfunction "P$2_H2") (pintype "bidirectional"))
      (node (ref "B19") (pin "S2") (pinfunction "IN_S2") (pintype "input"))
    )
    (net (code "152") (name "O_EXTA1") (class "Default")
      (node (ref "A23") (pin "E2") (pinfunction "P$2_E2") (pintype "bidirectional"))
      (node (ref "B19") (pin "P2") (pinfunction "IN_P2") (pintype "input"))
    )
    (net (code "153") (name "O_EXTA2") (class "Default")
      (node (ref "A23") (pin "D2") (pinfunction "P$2_D2") (pintype "bidirectional"))
      (node (ref "B19") (pin "M2") (pinfunction "IN_M2") (pintype "input"))
    )
    (net (code "154") (name "O_INIT") (class "Default")
      (node (ref "A14") (pin "V2") (pinfunction "P$2_V2") (pintype "bidirectional"))
      (node (ref "B09") (pin "S2") (pinfunction "OUT_S2") (pintype "output"))
    )
    (net (code "155") (name "O_IOP1") (class "Default")
      (node (ref "A14") (pin "K2") (pinfunction "P$2_K2") (pintype "bidirectional"))
      (node (ref "B08") (pin "D2") (pinfunction "OUT_D2") (pintype "output"))
    )
    (net (code "156") (name "O_IOP2") (class "Default")
      (node (ref "A14") (pin "M2") (pinfunction "P$2_M2") (pintype "bidirectional"))
      (node (ref "B08") (pin "K2") (pinfunction "OUT_K2") (pintype "output"))
    )
    (net (code "157") (name "O_IOP4") (class "Default")
      (node (ref "A14") (pin "P2") (pinfunction "P$2_P2") (pintype "bidirectional"))
      (node (ref "B08") (pin "S2") (pinfunction "OUT_S2") (pintype "output"))
    )
    (net (code "158") (name "O_IRQ") (class "Default")
      (node (ref "A18") (pin "M2") (pinfunction "P$2_M2") (pintype "bidirectional"))
      (node (ref "B18") (pin "H2") (pinfunction "IN_H2") (pintype "input"))
    )
    (net (code "159") (name "O_LINE") (class "Default")
      (node (ref "A18") (pin "V2") (pinfunction "P$2_V2") (pintype "bidirectional"))
      (node (ref "B18") (pin "M2") (pinfunction "IN_M2") (pintype "input"))
    )
    (net (code "160") (name "O_MB00") (class "Default")
      (node (ref "A07") (pin "D2") (pinfunction "OUT_D2") (pintype "output"))
      (node (ref "A15") (pin "D2") (pinfunction "P$2_D2") (pintype "bidirectional"))
    )
    (net (code "161") (name "O_MB01") (class "Default")
      (node (ref "A07") (pin "K2") (pinfunction "OUT_K2") (pintype "output"))
      (node (ref "A15") (pin "E2") (pinfunction "P$2_E2") (pintype "bidirectional"))
    )
    (net (code "162") (name "O_MB02") (class "Default")
      (node (ref "A07") (pin "S2") (pinfunction "OUT_S2") (pintype "output"))
      (node (ref "A15") (pin "H2") (pinfunction "P$2_H2") (pintype "bidirectional"))
    )
    (net (code "163") (name "O_MB03") (class "Default")
      (node (ref "A08") (pin "K2") (pinfunction "OUT_K2") (pintype "output"))
      (node (ref "A15") (pin "M2") (pinfunction "P$2_M2") (pintype "bidirectional"))
    )
    (net (code "164") (name "O_MB04") (class "Default")
      (node (ref "A09") (pin "D2") (pinfunction "OUT_D2") (pintype "output"))
      (node (ref "A15") (pin "S2") (pinfunction "P$2_S2") (pintype "bidirectional"))
    )
    (net (code "165") (name "O_MB05") (class "Default")
      (node (ref "A09") (pin "S2") (pinfunction "OUT_S2") (pintype "output"))
      (node (ref "A15") (pin "V2") (pinfunction "P$2_V2") (pintype "bidirectional"))
    )
    (net (code "166") (name "O_MB06") (class "Default")
      (node (ref "A10") (pin "K2") (pinfunction "OUT_K2") (pintype "output"))
      (node (ref "A16") (pin "E2") (pinfunction "P$2_E2") (pintype "bidirectional"))
    )
    (net (code "167") (name "O_MB07") (class "Default")
      (node (ref "A11") (pin "D2") (pinfunction "OUT_D2") (pintype "output"))
      (node (ref "A16") (pin "K2") (pinfunction "P$2_K2") (pintype "bidirectional"))
    )
    (net (code "168") (name "O_MB08") (class "Default")
      (node (ref "A11") (pin "S2") (pinfunction "OUT_S2") (pintype "output"))
      (node (ref "A16") (pin "P2") (pinfunction "P$2_P2") (pintype "bidirectional"))
    )
    (net (code "169") (name "O_MB09") (class "Default")
      (node (ref "A12") (pin "D2") (pinfunction "OUT_D2") (pintype "output"))
      (node (ref "A16") (pin "S2") (pinfunction "P$2_S2") (pintype "bidirectional"))
    )
    (net (code "170") (name "O_MB10") (class "Default")
      (node (ref "A12") (pin "K2") (pinfunction "OUT_K2") (pintype "output"))
      (node (ref "A16") (pin "T2") (pinfunction "P$2_T2") (pintype "bidirectional"))
    )
    (net (code "171") (name "O_MB11") (class "Default")
      (node (ref "A12") (pin "S2") (pinfunction "OUT_S2") (pintype "output"))
      (node (ref "A16") (pin "V2") (pinfunction "P$2_V2") (pintype "bidirectional"))
    )
    (net (code "172") (name "O_MBINCR") (class "Default")
      (node (ref "A20") (pin "T2") (pinfunction "P$2_T2") (pintype "bidirectional"))
      (node (ref "B19") (pin "E2") (pinfunction "IN_E2") (pintype "input"))
    )
    (net (code "173") (name "O_RUN") (class "Default")
      (node (ref "A18") (pin "S2") (pinfunction "P$2_S2") (pintype "bidirectional"))
      (node (ref "B14") (pin "D2") (pinfunction "OUT_D2") (pintype "output"))
    )
    (net (code "174") (name "O_SKIP") (class "Default")
      (node (ref "A18") (pin "K2") (pinfunction "P$2_K2") (pintype "bidirectional"))
      (node (ref "B18") (pin "E2") (pinfunction "IN_E2") (pintype "input"))
    )
    (net (code "175") (name "O_TS1") (class "Default")
      (node (ref "A14") (pin "T2") (pinfunction "P$2_T2") (pintype "bidirectional"))
      (node (ref "B09") (pin "K2") (pinfunction "OUT_K2") (pintype "output"))
    )
    (net (code "176") (name "O_TS3") (class "Default")
      (node (ref "A14") (pin "S2") (pinfunction "P$2_S2") (pintype "bidirectional"))
      (node (ref "B09") (pin "D2") (pinfunction "OUT_D2") (pintype "output"))
    )
    (net (code "177") (name "O_TT_INST") (class "Default")
      (node (ref "A18") (pin "T2") (pinfunction "P$2_T2") (pintype "bidirectional"))
      (node (ref "B14") (pin "K2") (pinfunction "OUT_K2") (pintype "output"))
    )
    (net (code "178") (name "O_WCOV") (class "Default")
      (node (ref "A22") (pin "P2") (pinfunction "P$2_P2") (pintype "bidirectional"))
      (node (ref "B15") (pin "K2") (pinfunction "OUT_K2") (pintype "output"))
    )
    (net (code "180") (name "unconnected-(A07A-SLOW-PadE2)") (class "Default")
      (node (ref "A07") (pin "E2") (pinfunction "SLOW_E2") (pintype "passive"))
    )
    (net (code "181") (name "unconnected-(A07D-SLOW-PadL2)") (class "Default")
      (node (ref "A07") (pin "L2") (pinfunction "SLOW_L2") (pintype "passive"))
    )
    (net (code "182") (name "unconnected-(A07E-SLOW-PadR2)") (class "Default")
      (node (ref "A07") (pin "R2") (pinfunction "SLOW_R2") (pintype "passive"))
    )
    (net (code "183") (name "unconnected-(A08A-SLOW-PadE2)") (class "Default")
      (node (ref "A08") (pin "E2") (pinfunction "SLOW_E2") (pintype "passive"))
    )
    (net (code "184") (name "unconnected-(A08D-SLOW-PadL2)") (class "Default")
      (node (ref "A08") (pin "L2") (pinfunction "SLOW_L2") (pintype "passive"))
    )
    (net (code "185") (name "unconnected-(A08E-SLOW-PadR2)") (class "Default")
      (node (ref "A08") (pin "R2") (pinfunction "SLOW_R2") (pintype "passive"))
    )
    (net (code "186") (name "unconnected-(A09A-SLOW-PadE2)") (class "Default")
      (node (ref "A09") (pin "E2") (pinfunction "SLOW_E2") (pintype "passive"))
    )
    (net (code "187") (name "unconnected-(A09D-SLOW-PadL2)") (class "Default")
      (node (ref "A09") (pin "L2") (pinfunction "SLOW_L2") (pintype "passive"))
    )
    (net (code "188") (name "unconnected-(A09E-SLOW-PadR2)") (class "Default")
      (node (ref "A09") (pin "R2") (pinfunction "SLOW_R2") (pintype "passive"))
    )
    (net (code "189") (name "unconnected-(A10A-SLOW-PadE2)") (class "Default")
      (node (ref "A10") (pin "E2") (pinfunction "SLOW_E2") (pintype "passive"))
    )
    (net (code "190") (name "unconnected-(A10D-SLOW-PadL2)") (class "Default")
      (node (ref "A10") (pin "L2") (pinfunction "SLOW_L2") (pintype "passive"))
    )
    (net (code "191") (name "unconnected-(A10E-SLOW-PadR2)") (class "Default")
      (node (ref "A10") (pin "R2") (pinfunction "SLOW_R2") (pintype "passive"))
    )
    (net (code "192") (name "unconnected-(A11A-SLOW-PadE2)") (class "Default")
      (node (ref "A11") (pin "E2") (pinfunction "SLOW_E2") (pintype "passive"))
    )
    (net (code "193") (name "unconnected-(A11D-SLOW-PadL2)") (class "Default")
      (node (ref "A11") (pin "L2") (pinfunction "SLOW_L2") (pintype "passive"))
    )
    (net (code "194") (name "unconnected-(A11E-SLOW-PadR2)") (class "Default")
      (node (ref "A11") (pin "R2") (pinfunction "SLOW_R2") (pintype "passive"))
    )
    (net (code "195") (name "unconnected-(A12A-SLOW-PadE2)") (class "Default")
      (node (ref "A12") (pin "E2") (pinfunction "SLOW_E2") (pintype "passive"))
    )
    (net (code "196") (name "unconnected-(A12D-SLOW-PadL2)") (class "Default")
      (node (ref "A12") (pin "L2") (pinfunction "SLOW_L2") (pintype "passive"))
    )
    (net (code "197") (name "unconnected-(A12E-SLOW-PadR2)") (class "Default")
      (node (ref "A12") (pin "R2") (pinfunction "SLOW_R2") (pintype "passive"))
    )
    (net (code "198") (name "unconnected-(B08A-SLOW-PadE2)") (class "Default")
      (node (ref "B08") (pin "E2") (pinfunction "SLOW_E2") (pintype "passive"))
    )
    (net (code "199") (name "unconnected-(B08D-SLOW-PadL2)") (class "Default")
      (node (ref "B08") (pin "L2") (pinfunction "SLOW_L2") (pintype "passive"))
    )
    (net (code "200") (name "unconnected-(B08E-SLOW-PadR2)") (class "Default")
      (node (ref "B08") (pin "R2") (pinfunction "SLOW_R2") (pintype "passive"))
    )
    (net (code "201") (name "unconnected-(B09A-SLOW-PadE2)") (class "Default")
      (node (ref "B09") (pin "E2") (pinfunction "SLOW_E2") (pintype "passive"))
    )
    (net (code "202") (name "unconnected-(B09D-SLOW-PadL2)") (class "Default")
      (node (ref "B09") (pin "L2") (pinfunction "SLOW_L2") (pintype "passive"))
    )
    (net (code "203") (name "unconnected-(B09E-SLOW-PadR2)") (class "Default")
      (node (ref "B09") (pin "R2") (pinfunction "SLOW_R2") (pintype "passive"))
    )
    (net (code "204") (name "unconnected-(B10A-SLOW-PadE2)") (class "Default")
      (node (ref "B10") (pin "E2") (pinfunction "SLOW_E2") (pintype "passive"))
    )
    (net (code "205") (name "unconnected-(B10D-SLOW-PadL2)") (class "Default")
      (node (ref "B10") (pin "L2") (pinfunction "SLOW_L2") (pintype "passive"))
    )
    (net (code "206") (name "unconnected-(B10E-SLOW-PadR2)") (class "Default")
      (node (ref "B10") (pin "R2") (pinfunction "SLOW_R2") (pintype "passive"))
    )
    (net (code "207") (name "unconnected-(B11A-SLOW-PadE2)") (class "Default")
      (node (ref "B11") (pin "E2") (pinfunction "SLOW_E2") (pintype "passive"))
    )
    (net (code "208") (name "unconnected-(B11D-SLOW-PadL2)") (class "Default")
      (node (ref "B11") (pin "L2") (pinfunction "SLOW_L2") (pintype "passive"))
    )
    (net (code "209") (name "unconnected-(B11E-SLOW-PadR2)") (class "Default")
      (node (ref "B11") (pin "R2") (pinfunction "SLOW_R2") (pintype "passive"))
    )
    (net (code "210") (name "unconnected-(B12A-SLOW-PadE2)") (class "Default")
      (node (ref "B12") (pin "E2") (pinfunction "SLOW_E2") (pintype "passive"))
    )
    (net (code "211") (name "unconnected-(B12D-SLOW-PadL2)") (class "Default")
      (node (ref "B12") (pin "L2") (pinfunction "SLOW_L2") (pintype "passive"))
    )
    (net (code "212") (name "unconnected-(B12E-SLOW-PadR2)") (class "Default")
      (node (ref "B12") (pin "R2") (pinfunction "SLOW_R2") (pintype "passive"))
    )
    (net (code "213") (name "unconnected-(B13A-SLOW-PadE2)") (class "Default")
      (node (ref "B13") (pin "E2") (pinfunction "SLOW_E2") (pintype "passive"))
    )
    (net (code "214") (name "unconnected-(B13D-SLOW-PadL2)") (class "Default")
      (node (ref "B13") (pin "L2") (pinfunction "SLOW_L2") (pintype "passive"))
    )
    (net (code "215") (name "unconnected-(B13E-SLOW-PadR2)") (class "Default")
      (node (ref "B13") (pin "R2") (pinfunction "SLOW_R2") (pintype "passive"))
    )
    (net (code "216") (name "unconnected-(B14A-SLOW-PadE2)") (class "Default")
      (node (ref "B14") (pin "E2") (pinfunction "SLOW_E2") (pintype "passive"))
    )
    (net (code "217") (name "unconnected-(B14D-SLOW-PadL2)") (class "Default")
      (node (ref "B14") (pin "L2") (pinfunction "SLOW_L2") (pintype "passive"))
    )
    (net (code "218") (name "unconnected-(B14E-SLOW-PadR2)") (class "Default")
      (node (ref "B14") (pin "R2") (pinfunction "SLOW_R2") (pintype "passive"))
    )
    (net (code "219") (name "unconnected-(B15A-SLOW-PadE2)") (class "Default")
      (node (ref "B15") (pin "E2") (pinfunction "SLOW_E2") (pintype "passive"))
    )
    (net (code "220") (name "unconnected-(B15D-SLOW-PadL2)") (class "Default")
      (node (ref "B15") (pin "L2") (pinfunction "SLOW_L2") (pintype "passive"))
    )
    (net (code "221") (name "~{I_MB03}") (class "Default")
      (node (ref "A02") (pin "H1") (pinfunction "P$2_H1") (pintype "bidirectional"))
      (node (ref "A06") (pin "H1") (pinfunction "CATHODE_H1") (pintype "passive"))
      (node (ref "A08") (pin "H2") (pinfunction "IN2_H2") (pintype "input"))
      (node (ref "B02") (pin "H1") (pinfunction "P$2_H1") (pintype "bidirectional"))
    )
    (net (code "222") (name "~{I_MB04}") (class "Default")
      (node (ref "A02") (pin "L1") (pinfunction "P$2_L1") (pintype "bidirectional"))
      (node (ref "A06") (pin "L1") (pinfunction "CATHODE_L1") (pintype "passive"))
      (node (ref "A08") (pin "U2") (pinfunction "IN2_U2") (pintype "input"))
      (node (ref "B02") (pin "L1") (pinfunction "P$2_L1") (pintype "bidirectional"))
    )
    (net (code "223") (name "~{I_MB05}") (class "Default")
      (node (ref "A02") (pin "P1") (pinfunction "P$2_P1") (pintype "bidirectional"))
      (node (ref "A06") (pin "P1") (pinfunction "CATHODE_P1") (pintype "passive"))
      (node (ref "A09") (pin "N2") (pinfunction "IN2_N2") (pintype "input"))
      (node (ref "B02") (pin "P1") (pinfunction "P$2_P1") (pintype "bidirectional"))
    )
    (net (code "224") (name "~{I_MB06}") (class "Default")
      (node (ref "A02") (pin "D2") (pinfunction "P$2_D2") (pintype "bidirectional"))
      (node (ref "A06") (pin "D2") (pinfunction "CATHODE_D2") (pintype "passive"))
      (node (ref "A10") (pin "H2") (pinfunction "IN2_H2") (pintype "input"))
      (node (ref "B02") (pin "D2") (pinfunction "P$2_D2") (pintype "bidirectional"))
    )
    (net (code "225") (name "~{I_MB07}") (class "Default")
      (node (ref "A02") (pin "H2") (pinfunction "P$2_H2") (pintype "bidirectional"))
      (node (ref "A06") (pin "H2") (pinfunction "CATHODE_H2") (pintype "passive"))
      (node (ref "A10") (pin "U2") (pinfunction "IN2_U2") (pintype "input"))
      (node (ref "B02") (pin "H2") (pinfunction "P$2_H2") (pintype "bidirectional"))
    )
    (net (code "226") (name "~{I_MB08}") (class "Default")
      (node (ref "A02") (pin "M2") (pinfunction "P$2_M2") (pintype "bidirectional"))
      (node (ref "A06") (pin "M2") (pinfunction "CATHODE_M2") (pintype "passive"))
      (node (ref "A11") (pin "N2") (pinfunction "IN2_N2") (pintype "input"))
      (node (ref "B02") (pin "M2") (pinfunction "P$2_M2") (pintype "bidirectional"))
    )
    (net (code "227") (name "~{O_MB03}") (class "Default")
      (node (ref "A08") (pin "D2") (pinfunction "OUT_D2") (pintype "output"))
      (node (ref "A15") (pin "K2") (pinfunction "P$2_K2") (pintype "bidirectional"))
    )
    (net (code "228") (name "~{O_MB04}") (class "Default")
      (node (ref "A08") (pin "S2") (pinfunction "OUT_S2") (pintype "output"))
      (node (ref "A15") (pin "P2") (pinfunction "P$2_P2") (pintype "bidirectional"))
    )
    (net (code "229") (name "~{O_MB05}") (class "Default")
      (node (ref "A09") (pin "K2") (pinfunction "OUT_K2") (pintype "output"))
      (node (ref "A15") (pin "T2") (pinfunction "P$2_T2") (pintype "bidirectional"))
    )
    (net (code "230") (name "~{O_MB06}") (class "Default")
      (node (ref "A10") (pin "D2") (pinfunction "OUT_D2") (pintype "output"))
      (node (ref "A16") (pin "D2") (pinfunction "P$2_D2") (pintype "bidirectional"))
    )
    (net (code "231") (name "~{O_MB07}") (class "Default")
      (node (ref "A10") (pin "S2") (pinfunction "OUT_S2") (pintype "output"))
      (node (ref "A16") (pin "H2") (pinfunction "P$2_H2") (pintype "bidirectional"))
    )
    (net (code "232") (name "~{O_MB08}") (class "Default")
      (node (ref "A11") (pin "K2") (pinfunction "OUT_K2") (pintype "output"))
      (node (ref "A16") (pin "M2") (pinfunction "P$2_M2") (pintype "bidirectional"))
    )
  )
)
